# Charger_Control_Board_rev8.net
KiCad netlist of a schematic drawn in EAGLE
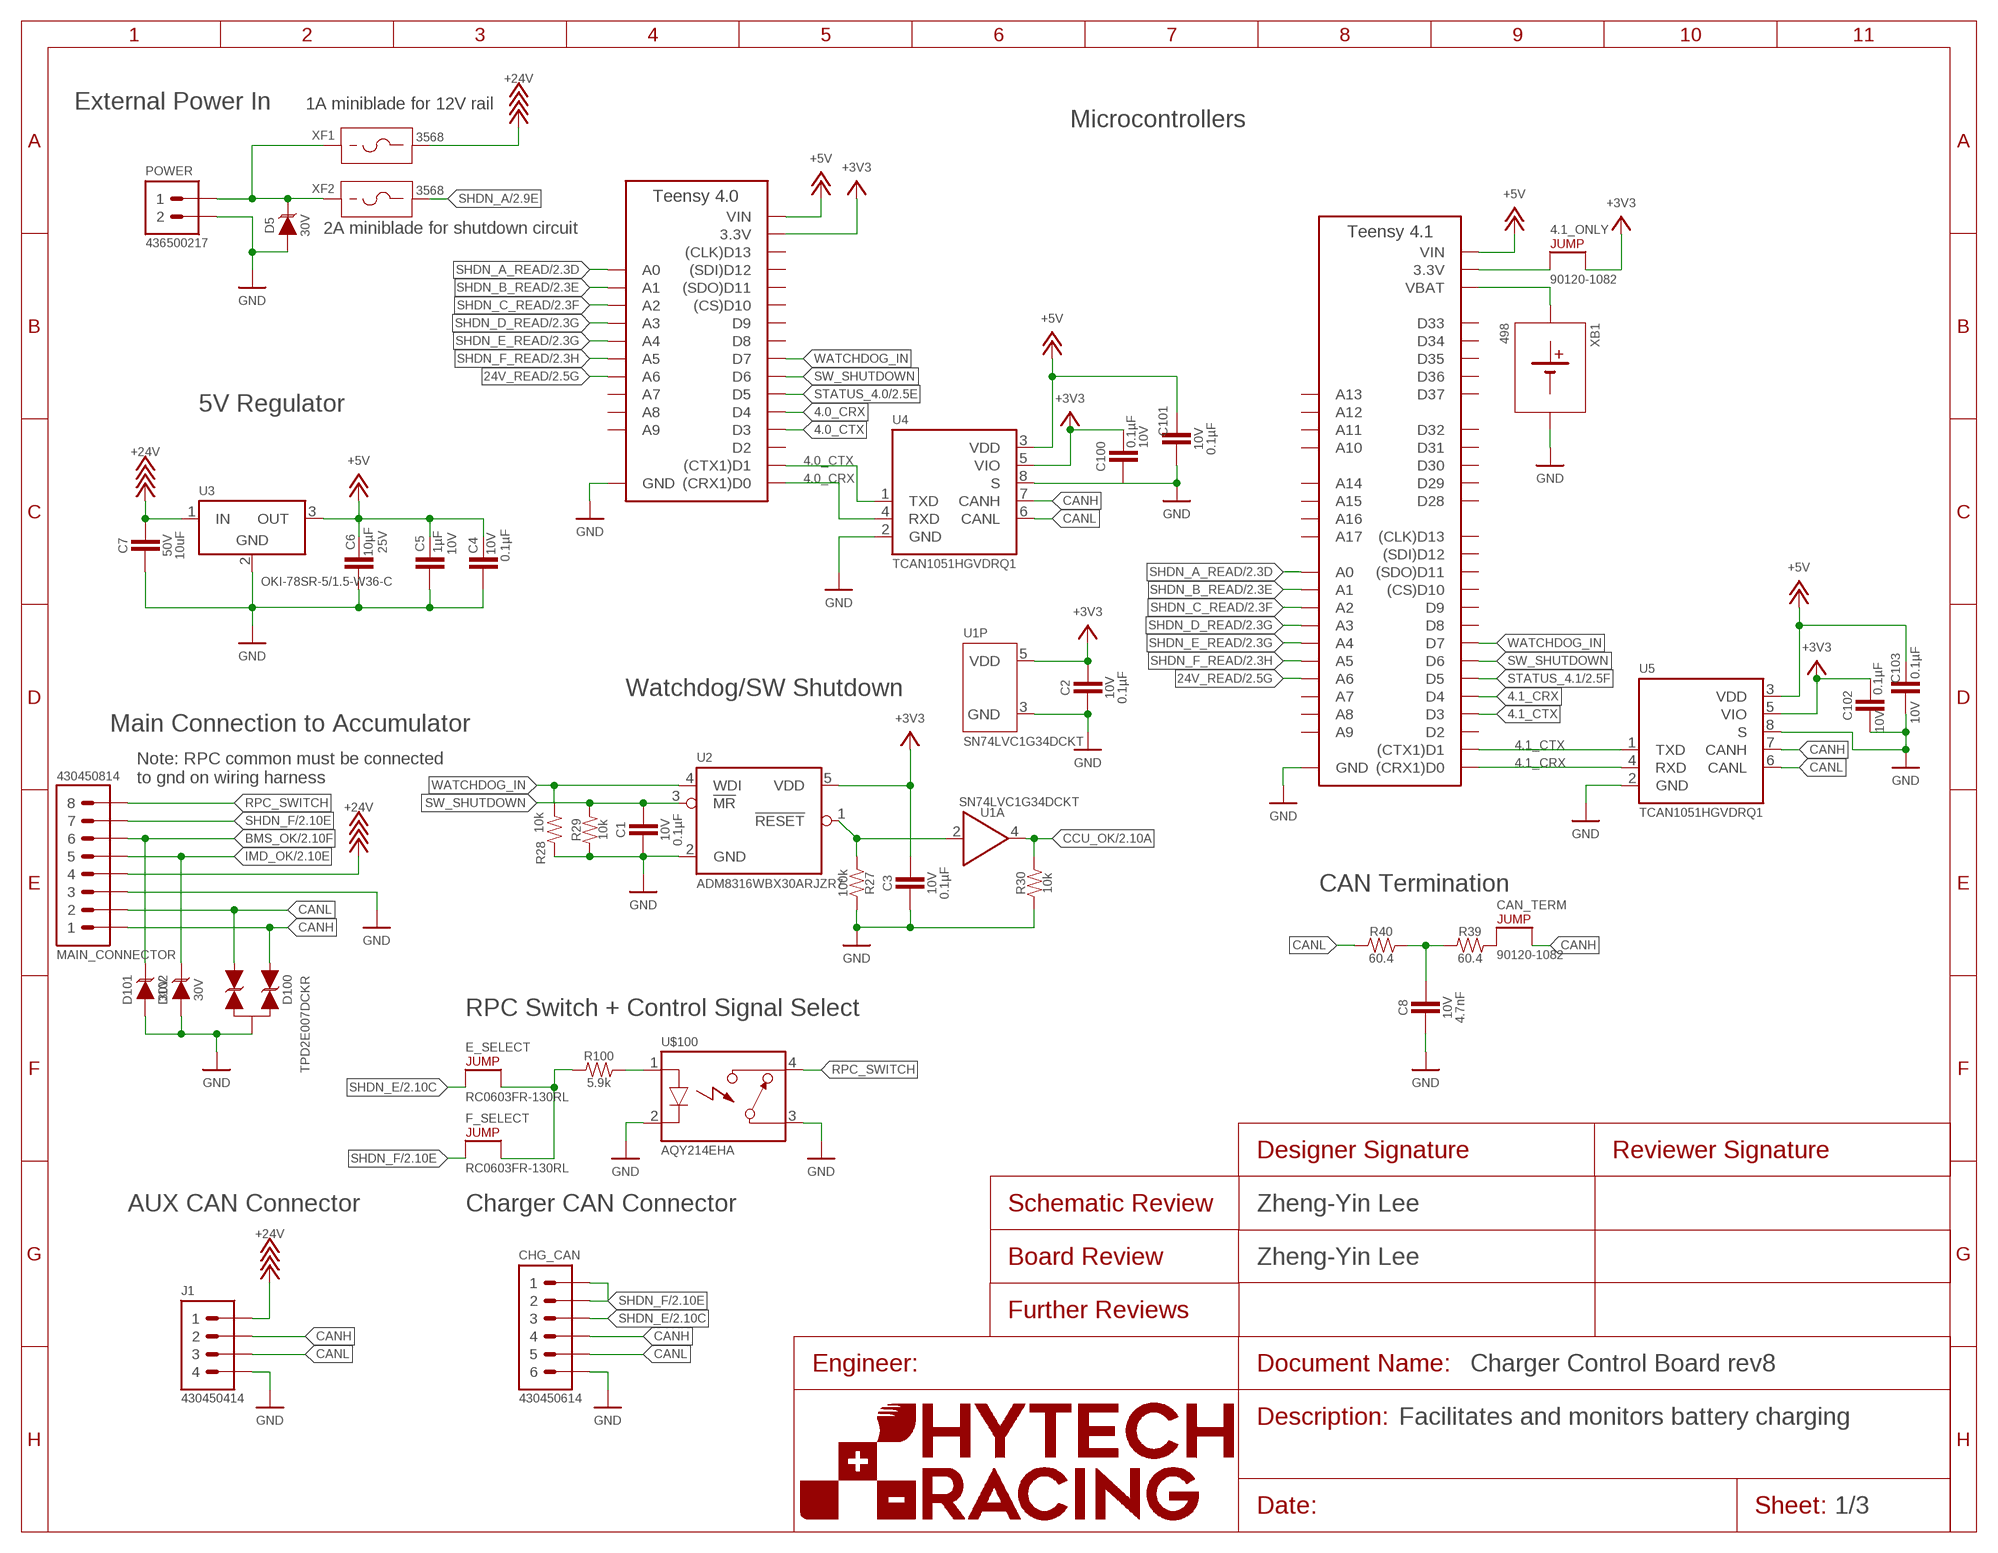
[diagram p0: schematic, sheet 1]
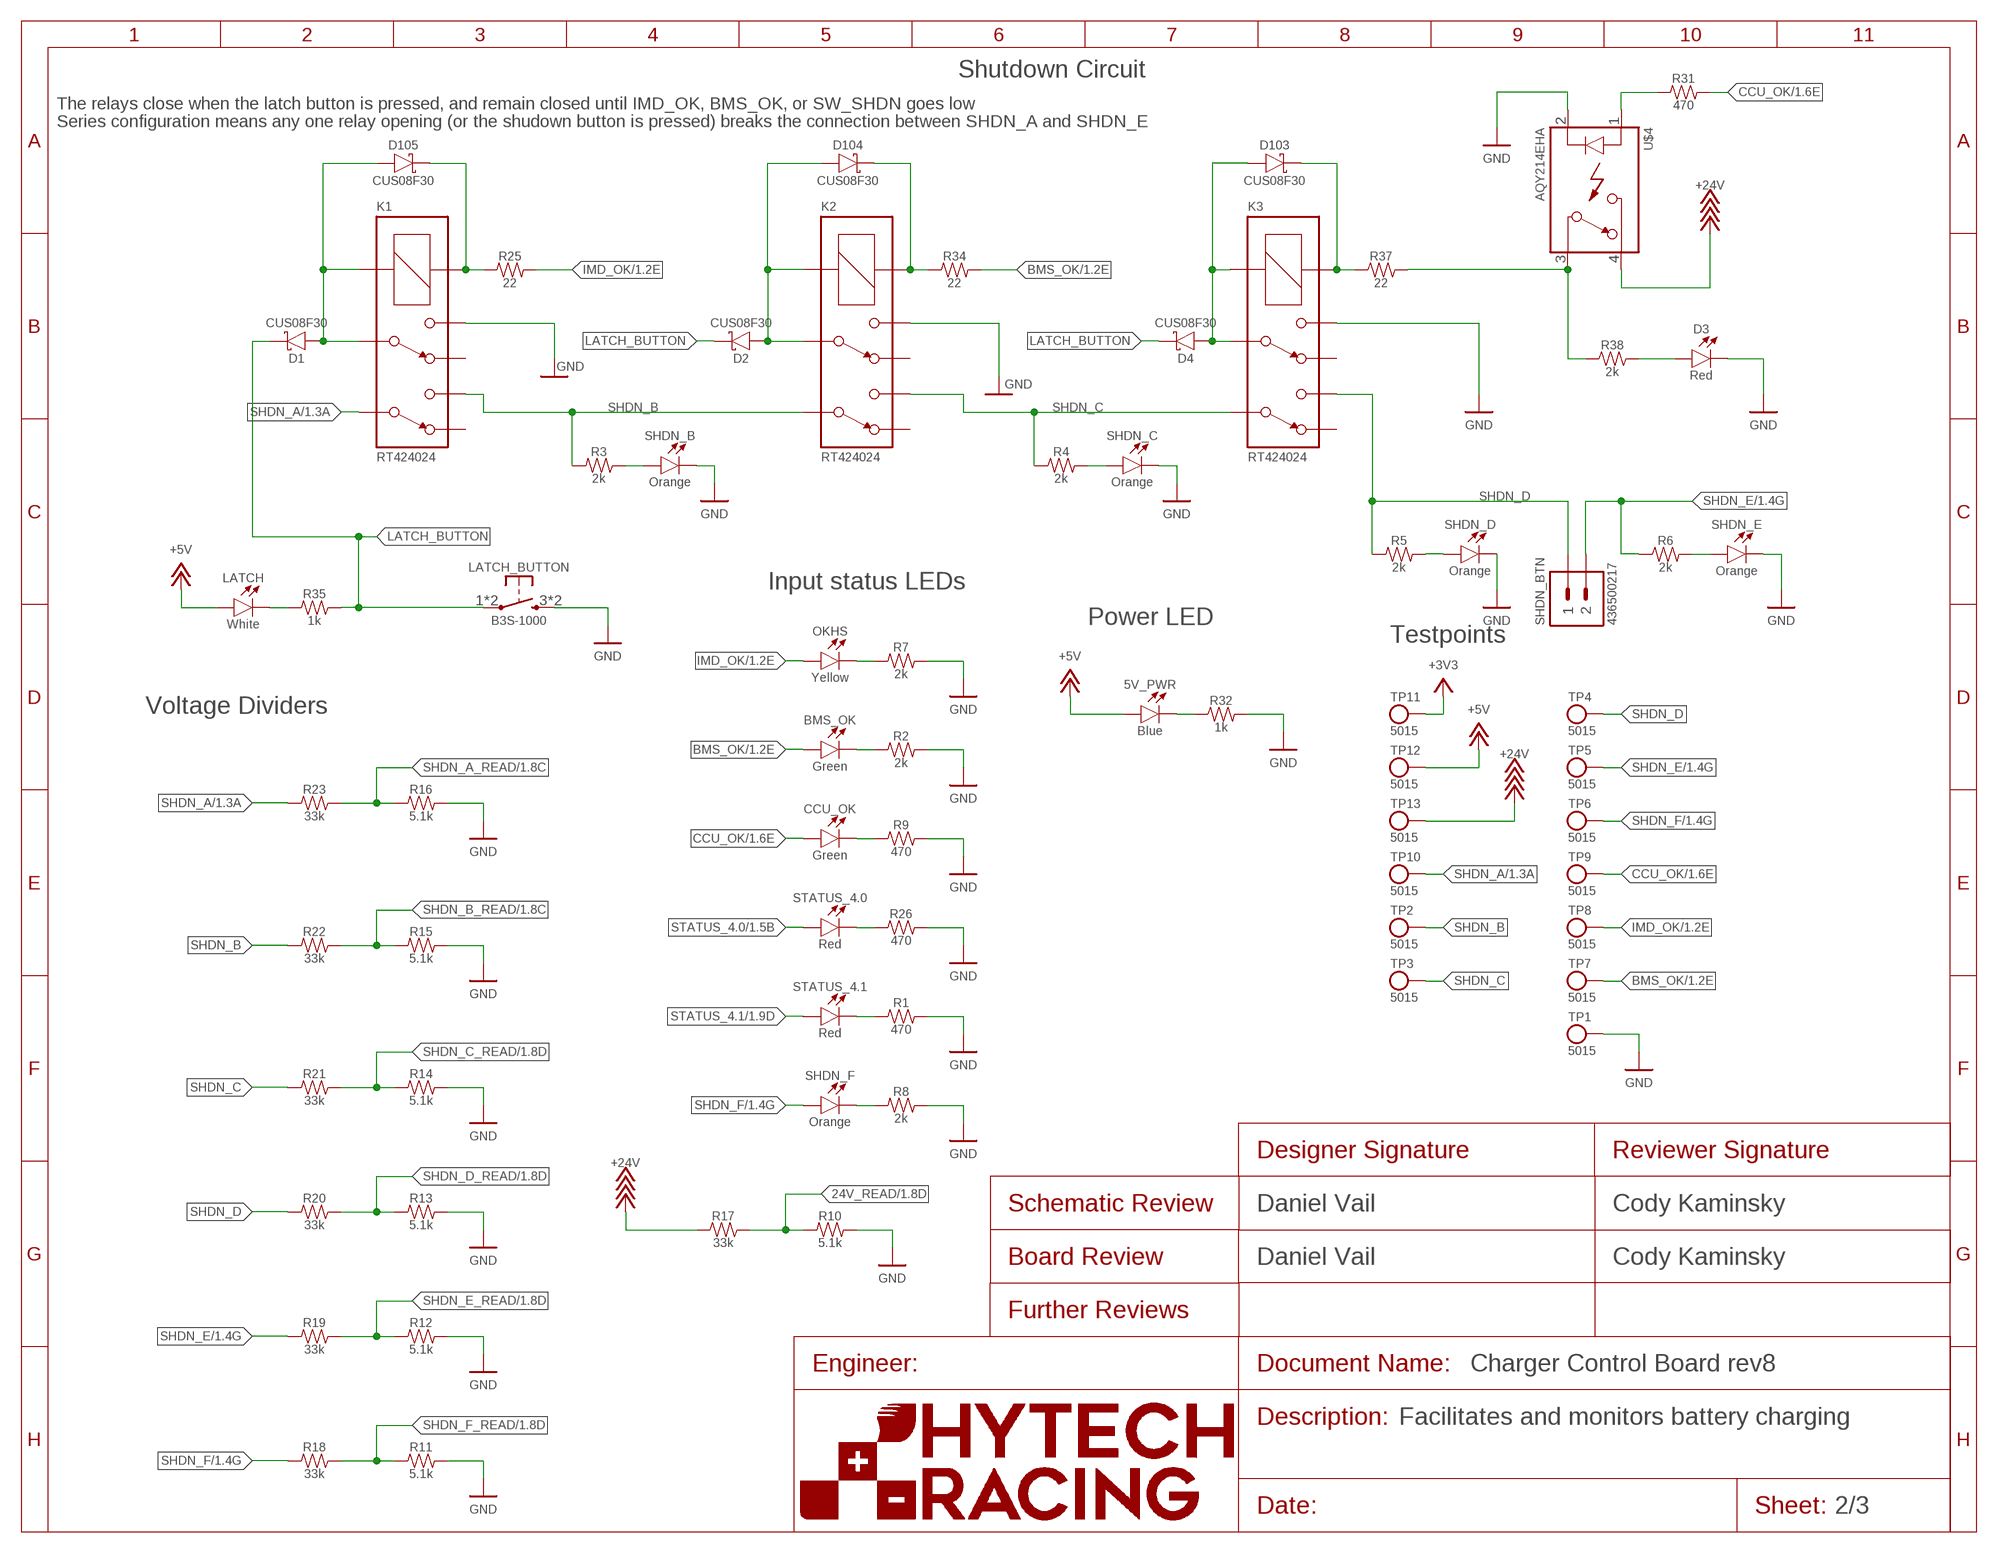
[diagram p1: schematic, sheet 2]
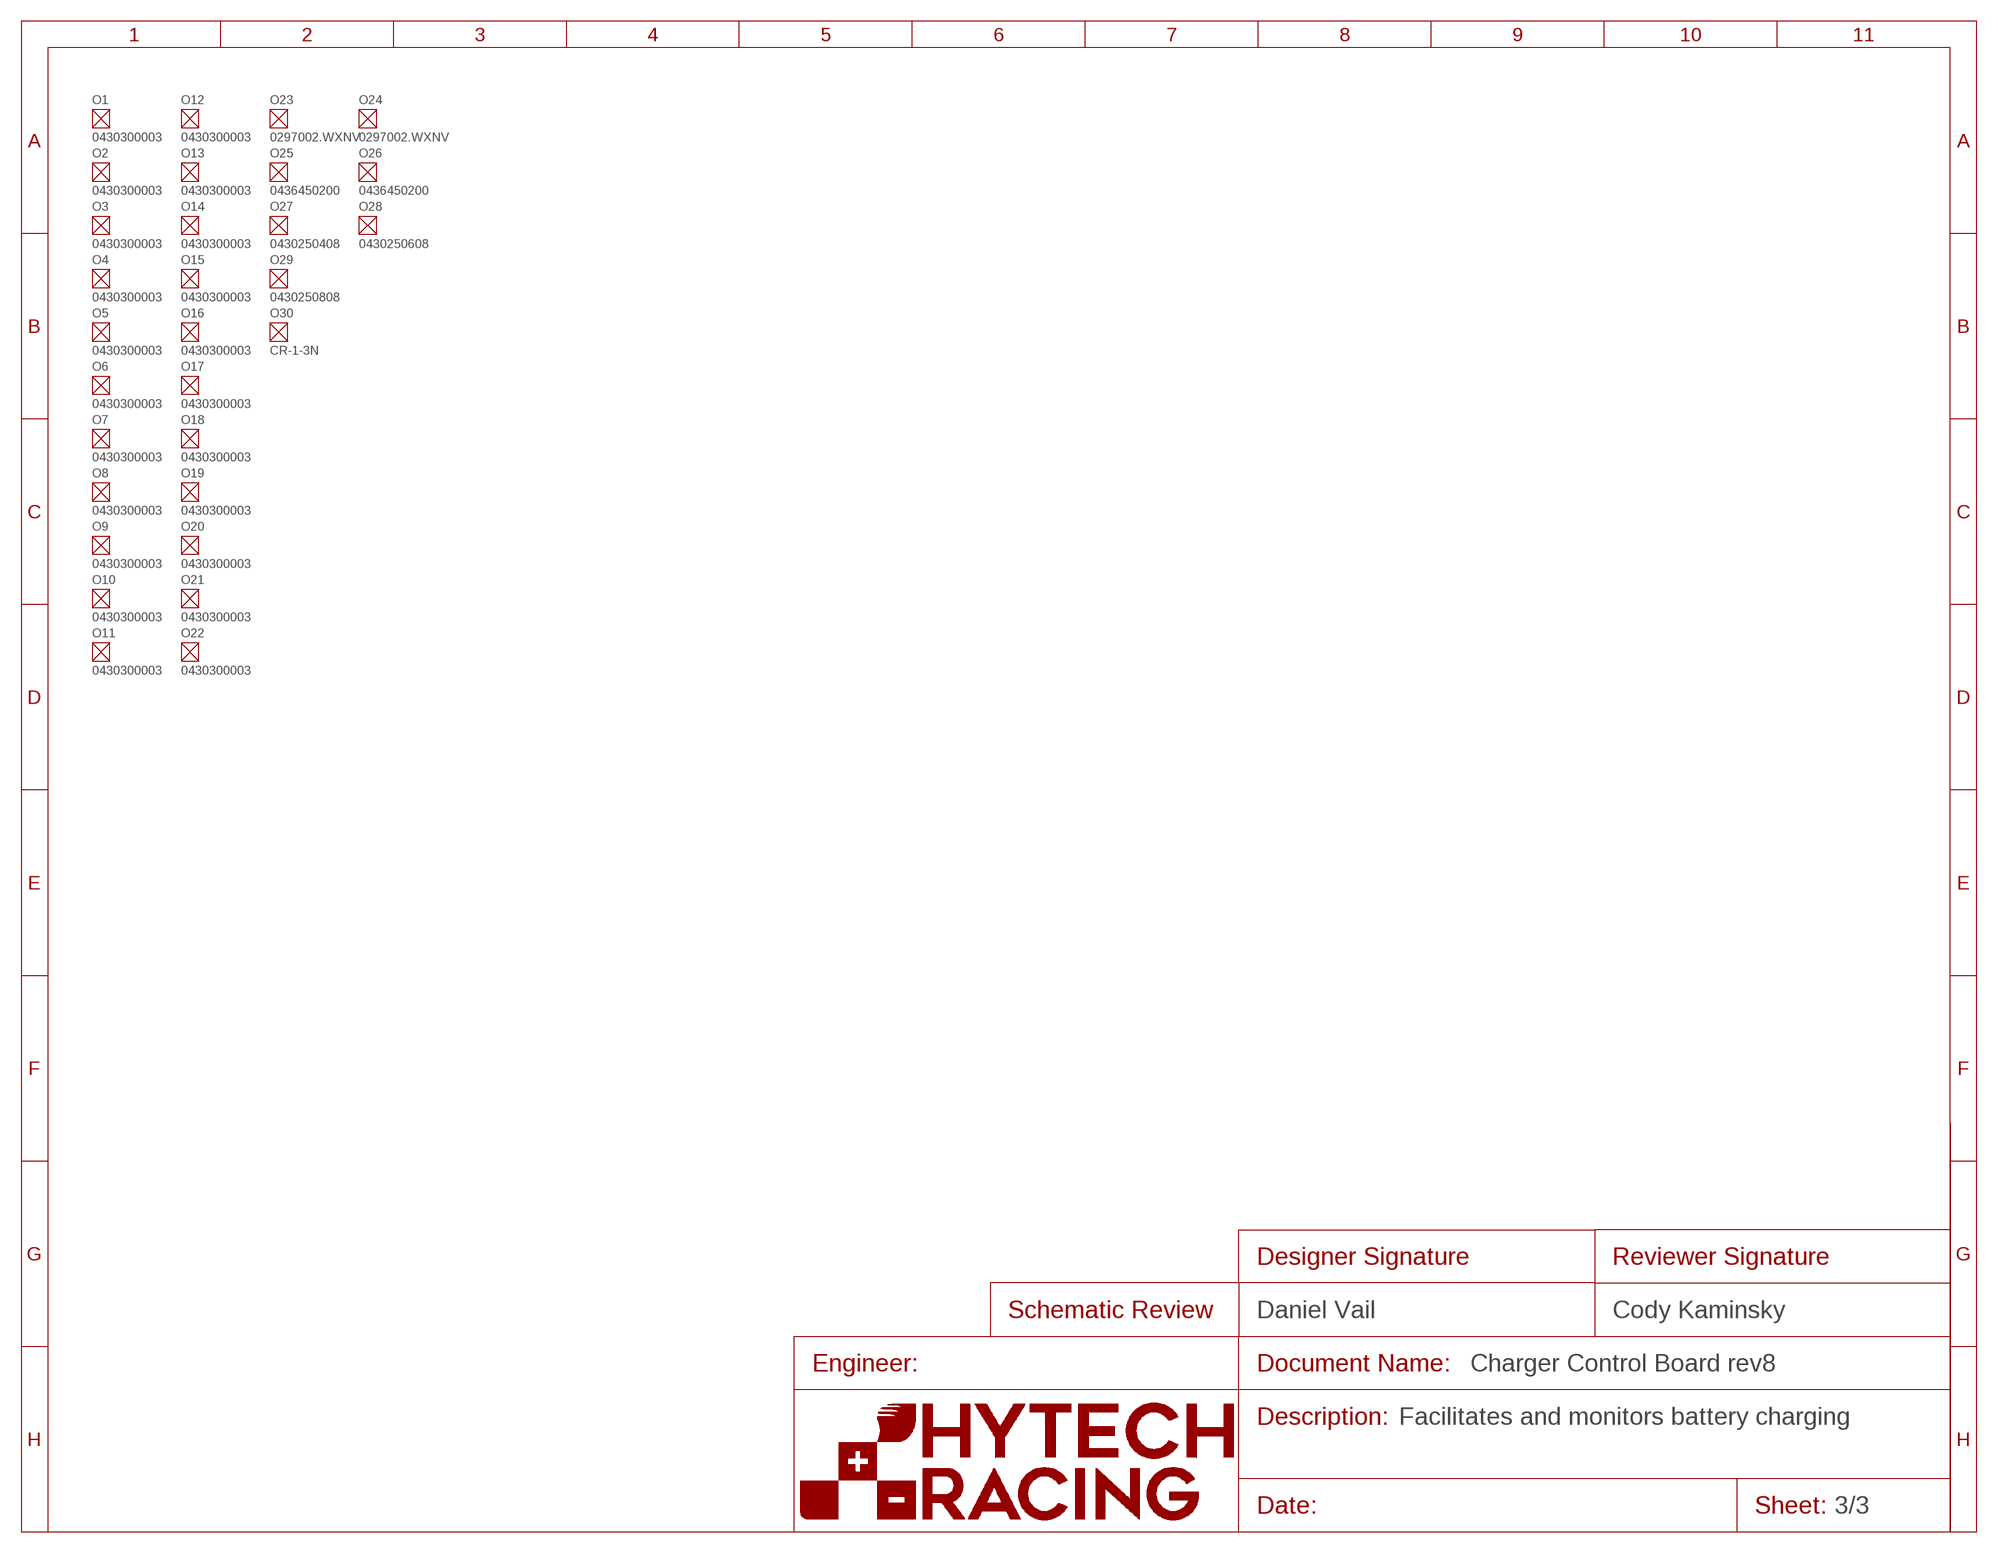
[diagram p2: schematic, sheet 3]

(export (version "E")
  (design (tool "Eeschema 10.0.6"))
  (components
    (comp (ref "4.1_ONLY")
      (value "JUMPER__1X02")
      (footprint "eagle-import:1X02")
      (fields (field (name "MANUFACTURER") "Molex") (field (name "MPN") "90120-1082 "))
      (libsource (lib "eagle-import") (part "JUMPER_?_1X02"))
    )
    (comp (ref "A1")
      (value "TEENSY_4.1")
      (footprint "eagle-import:TEENSY_LONG_EXT")
      (libsource (lib "eagle-import") (part "TEENSY_4.1"))
    )
    (comp (ref "A2")
      (value "TEENSY_4.0TH")
      (footprint "eagle-import:TEENSY_SHORT")
      (libsource (lib "eagle-import") (part "TEENSY_4.0TH"))
    )
    (comp (ref "C1")
      (value "CAPACITOR_0603_10V_0.1UF")
      (footprint "eagle-import:0603-CAP")
      (fields
        (field (name "CAPACITANCE") "0.1µF")
        (field (name "MANUFACTURER") "Vishay Vitramon")
        (field (name "MPN") "VJ0603Y104JXQPW1BC")
        (field (name "TOLERANCE") "5%")
        (field (name "VOLTAGE") "10V")
      )
      (libsource (lib "eagle-import") (part "CAPACITOR_?_060310V_0.1UF"))
    )
    (comp (ref "C2")
      (value "CAPACITOR_0603_10V_0.1UF")
      (footprint "eagle-import:0603-CAP")
      (fields
        (field (name "CAPACITANCE") "0.1µF")
        (field (name "MANUFACTURER") "Vishay Vitramon")
        (field (name "MPN") "VJ0603Y104JXQPW1BC")
        (field (name "TOLERANCE") "5%")
        (field (name "VOLTAGE") "10V")
      )
      (libsource (lib "eagle-import") (part "CAPACITOR_?_060310V_0.1UF"))
    )
    (comp (ref "C3")
      (value "CAPACITOR_0603_10V_0.1UF")
      (footprint "eagle-import:0603-CAP")
      (fields
        (field (name "CAPACITANCE") "0.1µF")
        (field (name "MANUFACTURER") "Vishay Vitramon")
        (field (name "MPN") "VJ0603Y104JXQPW1BC")
        (field (name "TOLERANCE") "5%")
        (field (name "VOLTAGE") "10V")
      )
      (libsource (lib "eagle-import") (part "CAPACITOR_?_060310V_0.1UF"))
    )
    (comp (ref "C4")
      (value "CAPACITOR_0603_10V_0.1UF")
      (footprint "eagle-import:0603-CAP")
      (fields
        (field (name "CAPACITANCE") "0.1µF")
        (field (name "MANUFACTURER") "Vishay Vitramon")
        (field (name "MPN") "VJ0603Y104JXQPW1BC")
        (field (name "TOLERANCE") "5%")
        (field (name "VOLTAGE") "10V")
      )
      (libsource (lib "eagle-import") (part "CAPACITOR_?_060310V_0.1UF"))
    )
    (comp (ref "C5")
      (value "CAPACITOR_0603_10V_1UF")
      (footprint "eagle-import:0603-CAP")
      (fields
        (field (name "CAPACITANCE") "1µF")
        (field (name "MANUFACTURER") "Yageo")
        (field (name "MPN") "CC0603KRX7R6BB105")
        (field (name "TOLERANCE") "10%")
        (field (name "VOLTAGE") "10V")
      )
      (libsource (lib "eagle-import") (part "CAPACITOR_?_060310V_1UF"))
    )
    (comp (ref "C6")
      (value "CAPACITOR_0603_25V_10UF")
      (footprint "eagle-import:0603-CAP")
      (fields
        (field (name "CAPACITANCE") "10µF")
        (field (name "MANUFACTURER") "Murata Electronics")
        (field (name "MPN") "GRM188R61E106MA73D")
        (field (name "TOLERANCE") "20%")
        (field (name "VOLTAGE") "25V")
      )
      (libsource (lib "eagle-import") (part "CAPACITOR_?_060325V_10UF"))
    )
    (comp (ref "C7")
      (value "CAPACITOR_0805_50V_10UF")
      (footprint "eagle-import:0805-CAP")
      (fields
        (field (name "CAPACITANCE") "10uF")
        (field (name "MANUFACTURER") "Murata")
        (field (name "MPN") " GRM21BR61H106KE43L")
        (field (name "TOLERANCE") "10%")
        (field (name "VOLTAGE") "50V")
      )
      (libsource (lib "eagle-import") (part "CAPACITOR_?_080550V_10UF"))
    )
    (comp (ref "C8")
      (value "CAPACITOR_0603_10V_4.7NF")
      (footprint "eagle-import:0603-CAP")
      (fields
        (field (name "CAPACITANCE") "4.7nF")
        (field (name "MANUFACTURER") "Würth Elektronik")
        (field (name "MPN") "885012206012")
        (field (name "TOLERANCE") "10%")
        (field (name "VOLTAGE") "10V")
      )
      (libsource (lib "eagle-import") (part "CAPACITOR_?_060310V_4.7NF"))
    )
    (comp (ref "C100")
      (value "CAPACITOR_0603_10V_0.1UF")
      (footprint "eagle-import:0603-CAP")
      (fields
        (field (name "CAPACITANCE") "0.1µF")
        (field (name "MANUFACTURER") "Vishay Vitramon")
        (field (name "MPN") "VJ0603Y104JXQPW1BC")
        (field (name "TOLERANCE") "5%")
        (field (name "VOLTAGE") "10V")
      )
      (libsource (lib "eagle-import") (part "CAPACITOR_?_060310V_0.1UF"))
    )
    (comp (ref "C101")
      (value "CAPACITOR_0603_10V_0.1UF")
      (footprint "eagle-import:0603-CAP")
      (fields
        (field (name "CAPACITANCE") "0.1µF")
        (field (name "MANUFACTURER") "Vishay Vitramon")
        (field (name "MPN") "VJ0603Y104JXQPW1BC")
        (field (name "TOLERANCE") "5%")
        (field (name "VOLTAGE") "10V")
      )
      (libsource (lib "eagle-import") (part "CAPACITOR_?_060310V_0.1UF"))
    )
    (comp (ref "C102")
      (value "CAPACITOR_0603_10V_0.1UF")
      (footprint "eagle-import:0603-CAP")
      (fields
        (field (name "CAPACITANCE") "0.1µF")
        (field (name "MANUFACTURER") "Vishay Vitramon")
        (field (name "MPN") "VJ0603Y104JXQPW1BC")
        (field (name "TOLERANCE") "5%")
        (field (name "VOLTAGE") "10V")
      )
      (libsource (lib "eagle-import") (part "CAPACITOR_?_060310V_0.1UF"))
    )
    (comp (ref "C103")
      (value "CAPACITOR_0603_10V_0.1UF")
      (footprint "eagle-import:0603-CAP")
      (fields
        (field (name "CAPACITANCE") "0.1µF")
        (field (name "MANUFACTURER") "Vishay Vitramon")
        (field (name "MPN") "VJ0603Y104JXQPW1BC")
        (field (name "TOLERANCE") "5%")
        (field (name "VOLTAGE") "10V")
      )
      (libsource (lib "eagle-import") (part "CAPACITOR_?_060310V_0.1UF"))
    )
    (comp (ref "CAN_TERM")
      (value "JUMPER__1X02")
      (footprint "eagle-import:1X02")
      (fields (field (name "MANUFACTURER") "Molex") (field (name "MPN") "90120-1082 "))
      (libsource (lib "eagle-import") (part "JUMPER_?_1X02"))
    )
    (comp (ref "CHG_CAN")
      (value "CONNECTOR-6_MF_T_V_")
      (footprint "eagle-import:MOLEX_MICROFIT_PTH_VERTICAL_06_DUAL")
      (fields (field (name "MPN") "430450614") (field (name "MANUFACTURER") "MOLEX"))
      (libsource (lib "eagle-import") (part "CONNECTOR-6_?_MF_T_V"))
    )
    (comp (ref "D5")
      (value "TVS_DO-214AA_30V")
      (footprint "eagle-import:DO-214AA")
      (fields
        (field (name "MANUFACTURER") "Bourns Inc.")
        (field (name "MPN") " 1.5SMBJ30A")
        (field (name "VOLTAGE") "30V")
      )
      (libsource (lib "eagle-import") (part "TVS_?_DO-214AA30V"))
    )
    (comp (ref "D100")
      (value "TVS_BIDIRECTIONAL_DUAL")
      (footprint "eagle-import:SC-70-3")
      (fields (field (name "MPN") "TPD2E007DCKR") (field (name "MANUFACTURER") "Texas Instruments"))
      (libsource (lib "eagle-import") (part "TVS_BIDIRECTIONAL_DUAL"))
    )
    (comp (ref "D101")
      (value "TVS_DO-214AA_30V")
      (footprint "eagle-import:DO-214AA")
      (fields
        (field (name "MANUFACTURER") "Bourns Inc.")
        (field (name "MPN") " 1.5SMBJ30A")
        (field (name "VOLTAGE") "30V")
      )
      (libsource (lib "eagle-import") (part "TVS_?_DO-214AA30V"))
    )
    (comp (ref "D102")
      (value "TVS_DO-214AA_30V")
      (footprint "eagle-import:DO-214AA")
      (fields
        (field (name "MANUFACTURER") "Bourns Inc.")
        (field (name "MPN") " 1.5SMBJ30A")
        (field (name "VOLTAGE") "30V")
      )
      (libsource (lib "eagle-import") (part "TVS_?_DO-214AA30V"))
    )
    (comp (ref "E_SELECT")
      (value "JUMPER_0603_")
      (footprint "eagle-import:0603-RES")
      (fields (field (name "MPN") "RC0603FR-130RL") (field (name "MANUFACTURER") "YAGEO"))
      (libsource (lib "eagle-import") (part "JUMPER_?_0603"))
    )
    (comp (ref "F_SELECT")
      (value "JUMPER_0603_")
      (footprint "eagle-import:0603-RES")
      (fields (field (name "MPN") "RC0603FR-130RL") (field (name "MANUFACTURER") "YAGEO"))
      (libsource (lib "eagle-import") (part "JUMPER_?_0603"))
    )
    (comp (ref "J1")
      (value "CONNECTOR-4_μF_T_V_BLACK")
      (footprint "eagle-import:MOLEX_MICROFIT_PTH_VERTICAL_04_DUAL")
      (fields (field (name "MANUFACTURER") "Molex") (field (name "MPN") "430450414"))
      (libsource (lib "eagle-import") (part "CONNECTOR-4_?_μF_T_VBLACK"))
    )
    (comp (ref "MAIN_CONNECTOR")
      (value "CONNECTOR-8_MF_T_V_")
      (footprint "eagle-import:MOLEX_MICROFIT_PTH_VERTICAL_08_DUAL")
      (fields (field (name "MPN") "430450814") (field (name "MANUFACTURER") "MOLEX"))
      (libsource (lib "eagle-import") (part "CONNECTOR-8_?_MF_T_V"))
    )
    (comp (ref "POWER")
      (value "CONNECTOR-2_μF_T_V_")
      (footprint "eagle-import:MOLEX_MICROFIT_PTH_VERTICAL_02_DUAL")
      (fields (field (name "MANUFACTURER") "Molex") (field (name "MPN") "436500217"))
      (libsource (lib "eagle-import") (part "CONNECTOR-2_?_μF_T_VBLACK"))
    )
    (comp (ref "R27")
      (value "RESISTOR_0603_100K")
      (footprint "eagle-import:0603-RES")
      (fields
        (field (name "MANUFACTURER") "Yageo")
        (field (name "MPN") "RC0603FR-07100KL")
        (field (name "POWER") "0.1W")
        (field (name "RESISTANCE") "100k")
      )
      (libsource (lib "eagle-import") (part "RESISTOR_?_0603100K"))
    )
    (comp (ref "R28")
      (value "RESISTOR_0603_10K")
      (footprint "eagle-import:0603-RES")
      (fields
        (field (name "MANUFACTURER") "Panasonic Electronic Components")
        (field (name "MPN") "ERA-3ARB103V")
        (field (name "POWER") "0.1W")
        (field (name "RESISTANCE") "10k")
      )
      (libsource (lib "eagle-import") (part "RESISTOR_?_060310K"))
    )
    (comp (ref "R29")
      (value "RESISTOR_0603_10K")
      (footprint "eagle-import:0603-RES")
      (fields
        (field (name "MANUFACTURER") "Panasonic Electronic Components")
        (field (name "MPN") "ERA-3ARB103V")
        (field (name "POWER") "0.1W")
        (field (name "RESISTANCE") "10k")
      )
      (libsource (lib "eagle-import") (part "RESISTOR_?_060310K"))
    )
    (comp (ref "R30")
      (value "RESISTOR_0603_10K")
      (footprint "eagle-import:0603-RES")
      (fields
        (field (name "MANUFACTURER") "Panasonic Electronic Components")
        (field (name "MPN") "ERA-3ARB103V")
        (field (name "POWER") "0.1W")
        (field (name "RESISTANCE") "10k")
      )
      (libsource (lib "eagle-import") (part "RESISTOR_?_060310K"))
    )
    (comp (ref "R39")
      (value "RESISTOR_0603_60.4")
      (footprint "eagle-import:0603-RES")
      (fields
        (field (name "MANUFACTURER") "Yageo")
        (field (name "MPN") "RC0603FR-0760R4L")
        (field (name "POWER") "0.1W")
        (field (name "RESISTANCE") "60.4")
      )
      (libsource (lib "eagle-import") (part "RESISTOR_?_060360.4"))
    )
    (comp (ref "R40")
      (value "RESISTOR_0603_60.4")
      (footprint "eagle-import:0603-RES")
      (fields
        (field (name "MANUFACTURER") "Yageo")
        (field (name "MPN") "RC0603FR-0760R4L")
        (field (name "POWER") "0.1W")
        (field (name "RESISTANCE") "60.4")
      )
      (libsource (lib "eagle-import") (part "RESISTOR_?_060360.4"))
    )
    (comp (ref "R100")
      (value "RESISTOR_0603_5.9K")
      (footprint "eagle-import:0603-RES")
      (fields
        (field (name "MANUFACTURER") "Panasonic Electronic Components")
        (field (name "MPN") "ERA-3AEB5901V")
        (field (name "POWER") "0.1W")
        (field (name "RESISTANCE") "5.9k")
      )
      (libsource (lib "eagle-import") (part "RESISTOR_?_06035.9K"))
    )
    (comp (ref "U$100")
      (value "RELAY_SOLIDSTATE_NO_DIP-4")
      (footprint "eagle-import:DIP-4")
      (fields (field (name "MPN") "AQY214EHA") (field (name "MANUFACTURER") "Panasonic"))
      (libsource (lib "eagle-import") (part "RELAY_SOLIDSTATE_NO_DIP-4"))
    )
    (comp (ref "U1")
      (value "LOGICGATE_BUFFER")
      (footprint "eagle-import:SC-70-5")
      (fields (field (name "MANUFACTURER") "Texas Instruments"))
      (libsource (lib "eagle-import") (part "LOGICGATE_BUFFER"))
    )
    (comp (ref "U2")
      (value "ADM8316WBX30")
      (footprint "eagle-import:SOT-23-5")
      (fields (field (name "MANUFACTURER") "Analog Devices Inc.") (field (name "MPN") "ADM8316WBX30ARJZR7"))
      (libsource (lib "eagle-import") (part "ADM8316WBX30"))
    )
    (comp (ref "U3")
      (value "VOLTAGE_REGULATOR_MODULE_OKI-78SR_5V")
      (footprint "eagle-import:OKI-78SR")
      (fields
        (field (name "MANUFACTURER") "Murata Power Solutions Inc.")
        (field (name "MPN") "OKI-78SR-5/1.5-W36-C")
      )
      (libsource (lib "eagle-import") (part "VOLTAGE_REGULATOR_MODULE_?_OKI-78SR5V"))
    )
    (comp (ref "U4")
      (value "TCAN1051HQV-Q1")
      (footprint "eagle-import:SOIC-08(NARROW,0.15_)")
      (fields (field (name "MANUFACTURER") "Texas Instruments") (field (name "MPN") "TCAN1051HGVDRQ1"))
      (libsource (lib "eagle-import") (part "TCAN1051V-Q1HQ"))
    )
    (comp (ref "U5")
      (value "TCAN1051HQV-Q1")
      (footprint "eagle-import:SOIC-08(NARROW,0.15_)")
      (fields (field (name "MANUFACTURER") "Texas Instruments") (field (name "MPN") "TCAN1051HGVDRQ1"))
      (libsource (lib "eagle-import") (part "TCAN1051V-Q1HQ"))
    )
    (comp (ref "XB1")
      (value "BATTERY_HOLDER_KEYSTONE_498")
      (footprint "eagle-import:498")
      (fields (field (name "MPN") "498") (field (name "MANUFACTURER") "Keystone Electronics"))
      (libsource (lib "eagle-import") (part "BATTERY_HOLDER_KEYSTONE_498"))
    )
    (comp (ref "XF1")
      (value "FUSE_HOLDER_MINIBLADEPTH")
      (footprint "eagle-import:3568")
      (fields (field (name "MANUFACTURER") "Keystone") (field (name "MPN") "3568"))
      (libsource (lib "eagle-import") (part "FUSE_HOLDER_PTHMINIBLADE"))
    )
    (comp (ref "XF2")
      (value "FUSE_HOLDER_MINIBLADEPTH")
      (footprint "eagle-import:3568")
      (fields (field (name "MANUFACTURER") "Keystone") (field (name "MPN") "3568"))
      (libsource (lib "eagle-import") (part "FUSE_HOLDER_PTHMINIBLADE"))
    )
    (comp (ref "5V_PWR")
      (value "LED_0603_BLUE")
      (footprint "eagle-import:0603-LED")
      (fields
        (field (name "COLOR") "Blue")
        (field (name "MANUFACTURER") "Kingbright")
        (field (name "MPN") "APT1608VBC/D")
      )
      (libsource (lib "eagle-import") (part "LED_?_0603BLUE"))
    )
    (comp (ref "BMS_OK")
      (value "LED_0603_GREEN")
      (footprint "eagle-import:0603-LED")
      (fields
        (field (name "COLOR") "Green")
        (field (name "MANUFACTURER") "Kingbright")
        (field (name "MPN") "APT1608ZGCK")
      )
      (libsource (lib "eagle-import") (part "LED_?_0603GREEN"))
    )
    (comp (ref "CCU_OK")
      (value "LED_0603_GREEN")
      (footprint "eagle-import:0603-LED")
      (fields
        (field (name "COLOR") "Green")
        (field (name "MANUFACTURER") "Kingbright")
        (field (name "MPN") "APT1608ZGCK")
      )
      (libsource (lib "eagle-import") (part "LED_?_0603GREEN"))
    )
    (comp (ref "D1")
      (value "SCHOTTKY_SOD323_30V")
      (footprint "eagle-import:SOD-323")
      (fields
        (field (name "MANUFACTURER") "Toshiba Semiconductor and Storage")
        (field (name "MPN") "CUS08F30")
        (field (name "VOLTAGE") "30V")
      )
      (libsource (lib "eagle-import") (part "SCHOTTKY_?_SOD32330V"))
    )
    (comp (ref "D2")
      (value "SCHOTTKY_SOD323_30V")
      (footprint "eagle-import:SOD-323")
      (fields
        (field (name "MANUFACTURER") "Toshiba Semiconductor and Storage")
        (field (name "MPN") "CUS08F30")
        (field (name "VOLTAGE") "30V")
      )
      (libsource (lib "eagle-import") (part "SCHOTTKY_?_SOD32330V"))
    )
    (comp (ref "D3")
      (value "LED_0603_RED")
      (footprint "eagle-import:0603-LED")
      (fields
        (field (name "COLOR") "Red")
        (field (name "MANUFACTURER") "Kingbright")
        (field (name "MPN") "APT1608SECK/J3-PRV")
      )
      (libsource (lib "eagle-import") (part "LED_?_0603RED"))
    )
    (comp (ref "D4")
      (value "SCHOTTKY_SOD323_30V")
      (footprint "eagle-import:SOD-323")
      (fields
        (field (name "MANUFACTURER") "Toshiba Semiconductor and Storage")
        (field (name "MPN") "CUS08F30")
        (field (name "VOLTAGE") "30V")
      )
      (libsource (lib "eagle-import") (part "SCHOTTKY_?_SOD32330V"))
    )
    (comp (ref "D103")
      (value "SCHOTTKY_SOD323_30V")
      (footprint "eagle-import:SOD-323")
      (fields
        (field (name "MANUFACTURER") "Toshiba Semiconductor and Storage")
        (field (name "MPN") "CUS08F30")
        (field (name "VOLTAGE") "30V")
      )
      (libsource (lib "eagle-import") (part "SCHOTTKY_?_SOD32330V"))
    )
    (comp (ref "D104")
      (value "SCHOTTKY_SOD323_30V")
      (footprint "eagle-import:SOD-323")
      (fields
        (field (name "MANUFACTURER") "Toshiba Semiconductor and Storage")
        (field (name "MPN") "CUS08F30")
        (field (name "VOLTAGE") "30V")
      )
      (libsource (lib "eagle-import") (part "SCHOTTKY_?_SOD32330V"))
    )
    (comp (ref "D105")
      (value "SCHOTTKY_SOD323_30V")
      (footprint "eagle-import:SOD-323")
      (fields
        (field (name "MANUFACTURER") "Toshiba Semiconductor and Storage")
        (field (name "MPN") "CUS08F30")
        (field (name "VOLTAGE") "30V")
      )
      (libsource (lib "eagle-import") (part "SCHOTTKY_?_SOD32330V"))
    )
    (comp (ref "K1")
      (value "RELAY_DPDT_RT424024TH")
      (footprint "eagle-import:RT_2_")
      (fields (field (name "MANUFACTURER") "TE Connectivity") (field (name "MPN") "RT424024"))
      (libsource (lib "eagle-import") (part "RELAY_DPDT_THRT424024"))
    )
    (comp (ref "K2")
      (value "RELAY_DPDT_RT424024TH")
      (footprint "eagle-import:RT_2_")
      (fields (field (name "MANUFACTURER") "TE Connectivity") (field (name "MPN") "RT424024"))
      (libsource (lib "eagle-import") (part "RELAY_DPDT_THRT424024"))
    )
    (comp (ref "K3")
      (value "RELAY_DPDT_RT424024TH")
      (footprint "eagle-import:RT_2_")
      (fields (field (name "MANUFACTURER") "TE Connectivity") (field (name "MPN") "RT424024"))
      (libsource (lib "eagle-import") (part "RELAY_DPDT_THRT424024"))
    )
    (comp (ref "LATCH")
      (value "LED_0603_WHITE")
      (footprint "eagle-import:0603-LED")
      (fields
        (field (name "COLOR") "White")
        (field (name "MANUFACTURER") "Bivar Inc.")
        (field (name "MPN") "SM0603UWC")
      )
      (libsource (lib "eagle-import") (part "LED_?_0603WHITE"))
    )
    (comp (ref "LATCH_BUTTON")
      (value "BUTTON")
      (footprint "eagle-import:B3S-100X")
      (fields (field (name "MPN") "B3S-1000") (field (name "MANUFACTURER") "Omron"))
      (libsource (lib "eagle-import") (part "BUTTON"))
    )
    (comp (ref "OKHS")
      (value "LED_0603_YELLOW")
      (footprint "eagle-import:0603-LED")
      (fields
        (field (name "COLOR") "Yellow")
        (field (name "MANUFACTURER") "Kingbright")
        (field (name "MPN") "APT1608SYCK/J3-PRV")
      )
      (libsource (lib "eagle-import") (part "LED_?_0603YELLOW"))
    )
    (comp (ref "R1")
      (value "RESISTOR_0603_470")
      (footprint "eagle-import:0603-RES")
      (fields
        (field (name "MANUFACTURER") "Panasonic Electronic Components")
        (field (name "MPN") "ERJ-PA3F4700V")
        (field (name "POWER") "0.25W")
        (field (name "RESISTANCE") "470")
      )
      (libsource (lib "eagle-import") (part "RESISTOR_?_0603470"))
    )
    (comp (ref "R2")
      (value "RESISTOR_0603_2K")
      (footprint "eagle-import:0603-RES")
      (fields
        (field (name "MANUFACTURER") "Panasonic Electronic Components")
        (field (name "MPN") "ERJ-UP3F2001V")
        (field (name "POWER") "0.25W")
        (field (name "RESISTANCE") "2k")
      )
      (libsource (lib "eagle-import") (part "RESISTOR_?_06032K"))
    )
    (comp (ref "R3")
      (value "RESISTOR_0603_2K")
      (footprint "eagle-import:0603-RES")
      (fields
        (field (name "MANUFACTURER") "Panasonic Electronic Components")
        (field (name "MPN") "ERJ-UP3F2001V")
        (field (name "POWER") "0.25W")
        (field (name "RESISTANCE") "2k")
      )
      (libsource (lib "eagle-import") (part "RESISTOR_?_06032K"))
    )
    (comp (ref "R4")
      (value "RESISTOR_0603_2K")
      (footprint "eagle-import:0603-RES")
      (fields
        (field (name "MANUFACTURER") "Panasonic Electronic Components")
        (field (name "MPN") "ERJ-UP3F2001V")
        (field (name "POWER") "0.25W")
        (field (name "RESISTANCE") "2k")
      )
      (libsource (lib "eagle-import") (part "RESISTOR_?_06032K"))
    )
    (comp (ref "R5")
      (value "RESISTOR_0603_2K")
      (footprint "eagle-import:0603-RES")
      (fields
        (field (name "MANUFACTURER") "Panasonic Electronic Components")
        (field (name "MPN") "ERJ-UP3F2001V")
        (field (name "POWER") "0.25W")
        (field (name "RESISTANCE") "2k")
      )
      (libsource (lib "eagle-import") (part "RESISTOR_?_06032K"))
    )
    (comp (ref "R6")
      (value "RESISTOR_0603_2K")
      (footprint "eagle-import:0603-RES")
      (fields
        (field (name "MANUFACTURER") "Panasonic Electronic Components")
        (field (name "MPN") "ERJ-UP3F2001V")
        (field (name "POWER") "0.25W")
        (field (name "RESISTANCE") "2k")
      )
      (libsource (lib "eagle-import") (part "RESISTOR_?_06032K"))
    )
    (comp (ref "R7")
      (value "RESISTOR_0603_2K")
      (footprint "eagle-import:0603-RES")
      (fields
        (field (name "MANUFACTURER") "Panasonic Electronic Components")
        (field (name "MPN") "ERJ-UP3F2001V")
        (field (name "POWER") "0.25W")
        (field (name "RESISTANCE") "2k")
      )
      (libsource (lib "eagle-import") (part "RESISTOR_?_06032K"))
    )
    (comp (ref "R8")
      (value "RESISTOR_0603_2K")
      (footprint "eagle-import:0603-RES")
      (fields
        (field (name "MANUFACTURER") "Panasonic Electronic Components")
        (field (name "MPN") "ERJ-UP3F2001V")
        (field (name "POWER") "0.25W")
        (field (name "RESISTANCE") "2k")
      )
      (libsource (lib "eagle-import") (part "RESISTOR_?_06032K"))
    )
    (comp (ref "R9")
      (value "RESISTOR_0603_470")
      (footprint "eagle-import:0603-RES")
      (fields
        (field (name "MANUFACTURER") "Panasonic Electronic Components")
        (field (name "MPN") "ERJ-PA3F4700V")
        (field (name "POWER") "0.25W")
        (field (name "RESISTANCE") "470")
      )
      (libsource (lib "eagle-import") (part "RESISTOR_?_0603470"))
    )
    (comp (ref "R10")
      (value "RESISTOR_0603_5.1K")
      (footprint "eagle-import:0603-RES")
      (fields
        (field (name "MANUFACTURER") "Yageo")
        (field (name "MPN") "RC0603FR-075K1L")
        (field (name "POWER") "0.1W")
        (field (name "RESISTANCE") "5.1k")
      )
      (libsource (lib "eagle-import") (part "RESISTOR_?_06035.1K"))
    )
    (comp (ref "R11")
      (value "RESISTOR_0603_5.1K")
      (footprint "eagle-import:0603-RES")
      (fields
        (field (name "MANUFACTURER") "Yageo")
        (field (name "MPN") "RC0603FR-075K1L")
        (field (name "POWER") "0.1W")
        (field (name "RESISTANCE") "5.1k")
      )
      (libsource (lib "eagle-import") (part "RESISTOR_?_06035.1K"))
    )
    (comp (ref "R12")
      (value "RESISTOR_0603_5.1K")
      (footprint "eagle-import:0603-RES")
      (fields
        (field (name "MANUFACTURER") "Yageo")
        (field (name "MPN") "RC0603FR-075K1L")
        (field (name "POWER") "0.1W")
        (field (name "RESISTANCE") "5.1k")
      )
      (libsource (lib "eagle-import") (part "RESISTOR_?_06035.1K"))
    )
    (comp (ref "R13")
      (value "RESISTOR_0603_5.1K")
      (footprint "eagle-import:0603-RES")
      (fields
        (field (name "MANUFACTURER") "Yageo")
        (field (name "MPN") "RC0603FR-075K1L")
        (field (name "POWER") "0.1W")
        (field (name "RESISTANCE") "5.1k")
      )
      (libsource (lib "eagle-import") (part "RESISTOR_?_06035.1K"))
    )
    (comp (ref "R14")
      (value "RESISTOR_0603_5.1K")
      (footprint "eagle-import:0603-RES")
      (fields
        (field (name "MANUFACTURER") "Yageo")
        (field (name "MPN") "RC0603FR-075K1L")
        (field (name "POWER") "0.1W")
        (field (name "RESISTANCE") "5.1k")
      )
      (libsource (lib "eagle-import") (part "RESISTOR_?_06035.1K"))
    )
    (comp (ref "R15")
      (value "RESISTOR_0603_5.1K")
      (footprint "eagle-import:0603-RES")
      (fields
        (field (name "MANUFACTURER") "Yageo")
        (field (name "MPN") "RC0603FR-075K1L")
        (field (name "POWER") "0.1W")
        (field (name "RESISTANCE") "5.1k")
      )
      (libsource (lib "eagle-import") (part "RESISTOR_?_06035.1K"))
    )
    (comp (ref "R16")
      (value "RESISTOR_0603_5.1K")
      (footprint "eagle-import:0603-RES")
      (fields
        (field (name "MANUFACTURER") "Yageo")
        (field (name "MPN") "RC0603FR-075K1L")
        (field (name "POWER") "0.1W")
        (field (name "RESISTANCE") "5.1k")
      )
      (libsource (lib "eagle-import") (part "RESISTOR_?_06035.1K"))
    )
    (comp (ref "R17")
      (value "RESISTOR_0603_33K")
      (footprint "eagle-import:0603-RES")
      (fields
        (field (name "MANUFACTURER") "Rohm Semiconductor")
        (field (name "MPN") "KTR03EZPF3302")
        (field (name "POWER") "0.1W")
        (field (name "RESISTANCE") "33k")
      )
      (libsource (lib "eagle-import") (part "RESISTOR_?_060333K"))
    )
    (comp (ref "R18")
      (value "RESISTOR_0603_33K")
      (footprint "eagle-import:0603-RES")
      (fields
        (field (name "MANUFACTURER") "Rohm Semiconductor")
        (field (name "MPN") "KTR03EZPF3302")
        (field (name "POWER") "0.1W")
        (field (name "RESISTANCE") "33k")
      )
      (libsource (lib "eagle-import") (part "RESISTOR_?_060333K"))
    )
    (comp (ref "R19")
      (value "RESISTOR_0603_33K")
      (footprint "eagle-import:0603-RES")
      (fields
        (field (name "MANUFACTURER") "Rohm Semiconductor")
        (field (name "MPN") "KTR03EZPF3302")
        (field (name "POWER") "0.1W")
        (field (name "RESISTANCE") "33k")
      )
      (libsource (lib "eagle-import") (part "RESISTOR_?_060333K"))
    )
    (comp (ref "R20")
      (value "RESISTOR_0603_33K")
      (footprint "eagle-import:0603-RES")
      (fields
        (field (name "MANUFACTURER") "Rohm Semiconductor")
        (field (name "MPN") "KTR03EZPF3302")
        (field (name "POWER") "0.1W")
        (field (name "RESISTANCE") "33k")
      )
      (libsource (lib "eagle-import") (part "RESISTOR_?_060333K"))
    )
    (comp (ref "R21")
      (value "RESISTOR_0603_33K")
      (footprint "eagle-import:0603-RES")
      (fields
        (field (name "MANUFACTURER") "Rohm Semiconductor")
        (field (name "MPN") "KTR03EZPF3302")
        (field (name "POWER") "0.1W")
        (field (name "RESISTANCE") "33k")
      )
      (libsource (lib "eagle-import") (part "RESISTOR_?_060333K"))
    )
    (comp (ref "R22")
      (value "RESISTOR_0603_33K")
      (footprint "eagle-import:0603-RES")
      (fields
        (field (name "MANUFACTURER") "Rohm Semiconductor")
        (field (name "MPN") "KTR03EZPF3302")
        (field (name "POWER") "0.1W")
        (field (name "RESISTANCE") "33k")
      )
      (libsource (lib "eagle-import") (part "RESISTOR_?_060333K"))
    )
    (comp (ref "R23")
      (value "RESISTOR_0603_33K")
      (footprint "eagle-import:0603-RES")
      (fields
        (field (name "MANUFACTURER") "Rohm Semiconductor")
        (field (name "MPN") "KTR03EZPF3302")
        (field (name "POWER") "0.1W")
        (field (name "RESISTANCE") "33k")
      )
      (libsource (lib "eagle-import") (part "RESISTOR_?_060333K"))
    )
    (comp (ref "R25")
      (value "RESISTOR_0603_22")
      (footprint "eagle-import:0603-RES")
      (fields
        (field (name "MANUFACTURER") "Yageo")
        (field (name "MPN") "RC0603FR-0722RL")
        (field (name "POWER") "0.1W")
        (field (name "RESISTANCE") "22")
      )
      (libsource (lib "eagle-import") (part "RESISTOR_?_060322"))
    )
    (comp (ref "R26")
      (value "RESISTOR_0603_470")
      (footprint "eagle-import:0603-RES")
      (fields
        (field (name "MANUFACTURER") "Panasonic Electronic Components")
        (field (name "MPN") "ERJ-PA3F4700V")
        (field (name "POWER") "0.25W")
        (field (name "RESISTANCE") "470")
      )
      (libsource (lib "eagle-import") (part "RESISTOR_?_0603470"))
    )
    (comp (ref "R31")
      (value "RESISTOR_0603_470")
      (footprint "eagle-import:0603-RES")
      (fields
        (field (name "MANUFACTURER") "Panasonic Electronic Components")
        (field (name "MPN") "ERJ-PA3F4700V")
        (field (name "POWER") "0.25W")
        (field (name "RESISTANCE") "470")
      )
      (libsource (lib "eagle-import") (part "RESISTOR_?_0603470"))
    )
    (comp (ref "R32")
      (value "RESISTOR_0603_1K")
      (footprint "eagle-import:0603-RES")
      (fields
        (field (name "MANUFACTURER") "TE Connectivity Passive Product")
        (field (name "MPN") " CPF-A-0603B1K0E")
        (field (name "POWER") "0.0625W")
        (field (name "RESISTANCE") "1k")
      )
      (libsource (lib "eagle-import") (part "RESISTOR_?_06031K"))
    )
    (comp (ref "R34")
      (value "RESISTOR_0603_22")
      (footprint "eagle-import:0603-RES")
      (fields
        (field (name "MANUFACTURER") "Yageo")
        (field (name "MPN") "RC0603FR-0722RL")
        (field (name "POWER") "0.1W")
        (field (name "RESISTANCE") "22")
      )
      (libsource (lib "eagle-import") (part "RESISTOR_?_060322"))
    )
    (comp (ref "R35")
      (value "RESISTOR_0603_1K")
      (footprint "eagle-import:0603-RES")
      (fields
        (field (name "MANUFACTURER") "TE Connectivity Passive Product")
        (field (name "MPN") " CPF-A-0603B1K0E")
        (field (name "POWER") "0.0625W")
        (field (name "RESISTANCE") "1k")
      )
      (libsource (lib "eagle-import") (part "RESISTOR_?_06031K"))
    )
    (comp (ref "R37")
      (value "RESISTOR_0603_22")
      (footprint "eagle-import:0603-RES")
      (fields
        (field (name "MANUFACTURER") "Yageo")
        (field (name "MPN") "RC0603FR-0722RL")
        (field (name "POWER") "0.1W")
        (field (name "RESISTANCE") "22")
      )
      (libsource (lib "eagle-import") (part "RESISTOR_?_060322"))
    )
    (comp (ref "R38")
      (value "RESISTOR_0603_2K")
      (footprint "eagle-import:0603-RES")
      (fields
        (field (name "MANUFACTURER") "Panasonic Electronic Components")
        (field (name "MPN") "ERJ-UP3F2001V")
        (field (name "POWER") "0.25W")
        (field (name "RESISTANCE") "2k")
      )
      (libsource (lib "eagle-import") (part "RESISTOR_?_06032K"))
    )
    (comp (ref "SHDN_B")
      (value "LED_0603_ORANGE")
      (footprint "eagle-import:0603-LED")
      (fields
        (field (name "COLOR") "Orange")
        (field (name "MANUFACTURER") "Kingbright")
        (field (name "MPN") "APT1608SECK")
      )
      (libsource (lib "eagle-import") (part "LED_?_0603ORANGE"))
    )
    (comp (ref "SHDN_BTN")
      (value "CONNECTOR-2_μF_T_V_")
      (footprint "eagle-import:MOLEX_MICROFIT_PTH_VERTICAL_02_DUAL")
      (fields (field (name "MANUFACTURER") "Molex") (field (name "MPN") "436500217"))
      (libsource (lib "eagle-import") (part "CONNECTOR-2_?_μF_T_VBLACK"))
    )
    (comp (ref "SHDN_C")
      (value "LED_0603_ORANGE")
      (footprint "eagle-import:0603-LED")
      (fields
        (field (name "COLOR") "Orange")
        (field (name "MANUFACTURER") "Kingbright")
        (field (name "MPN") "APT1608SECK")
      )
      (libsource (lib "eagle-import") (part "LED_?_0603ORANGE"))
    )
    (comp (ref "SHDN_D")
      (value "LED_0603_ORANGE")
      (footprint "eagle-import:0603-LED")
      (fields
        (field (name "COLOR") "Orange")
        (field (name "MANUFACTURER") "Kingbright")
        (field (name "MPN") "APT1608SECK")
      )
      (libsource (lib "eagle-import") (part "LED_?_0603ORANGE"))
    )
    (comp (ref "SHDN_E")
      (value "LED_0603_ORANGE")
      (footprint "eagle-import:0603-LED")
      (fields
        (field (name "COLOR") "Orange")
        (field (name "MANUFACTURER") "Kingbright")
        (field (name "MPN") "APT1608SECK")
      )
      (libsource (lib "eagle-import") (part "LED_?_0603ORANGE"))
    )
    (comp (ref "SHDN_F")
      (value "LED_0603_ORANGE")
      (footprint "eagle-import:0603-LED")
      (fields
        (field (name "COLOR") "Orange")
        (field (name "MANUFACTURER") "Kingbright")
        (field (name "MPN") "APT1608SECK")
      )
      (libsource (lib "eagle-import") (part "LED_?_0603ORANGE"))
    )
    (comp (ref "STATUS_4.0")
      (value "LED_0603_RED")
      (footprint "eagle-import:0603-LED")
      (fields
        (field (name "COLOR") "Red")
        (field (name "MANUFACTURER") "Kingbright")
        (field (name "MPN") "APT1608SECK/J3-PRV")
      )
      (libsource (lib "eagle-import") (part "LED_?_0603RED"))
    )
    (comp (ref "STATUS_4.1")
      (value "LED_0603_RED")
      (footprint "eagle-import:0603-LED")
      (fields
        (field (name "COLOR") "Red")
        (field (name "MANUFACTURER") "Kingbright")
        (field (name "MPN") "APT1608SECK/J3-PRV")
      )
      (libsource (lib "eagle-import") (part "LED_?_0603RED"))
    )
    (comp (ref "TP1")
      (value "TEST_POINT")
      (footprint "eagle-import:5015")
      (fields (field (name "MPN") "5015") (field (name "MANUFACTURER") "Keystone Electronics"))
      (libsource (lib "eagle-import") (part "TEST_POINT"))
    )
    (comp (ref "TP2")
      (value "TEST_POINT")
      (footprint "eagle-import:5015")
      (fields (field (name "MPN") "5015") (field (name "MANUFACTURER") "Keystone Electronics"))
      (libsource (lib "eagle-import") (part "TEST_POINT"))
    )
    (comp (ref "TP3")
      (value "TEST_POINT")
      (footprint "eagle-import:5015")
      (fields (field (name "MPN") "5015") (field (name "MANUFACTURER") "Keystone Electronics"))
      (libsource (lib "eagle-import") (part "TEST_POINT"))
    )
    (comp (ref "TP4")
      (value "TEST_POINT")
      (footprint "eagle-import:5015")
      (fields (field (name "MPN") "5015") (field (name "MANUFACTURER") "Keystone Electronics"))
      (libsource (lib "eagle-import") (part "TEST_POINT"))
    )
    (comp (ref "TP5")
      (value "TEST_POINT")
      (footprint "eagle-import:5015")
      (fields (field (name "MPN") "5015") (field (name "MANUFACTURER") "Keystone Electronics"))
      (libsource (lib "eagle-import") (part "TEST_POINT"))
    )
    (comp (ref "TP6")
      (value "TEST_POINT")
      (footprint "eagle-import:5015")
      (fields (field (name "MPN") "5015") (field (name "MANUFACTURER") "Keystone Electronics"))
      (libsource (lib "eagle-import") (part "TEST_POINT"))
    )
    (comp (ref "TP7")
      (value "TEST_POINT")
      (footprint "eagle-import:5015")
      (fields (field (name "MPN") "5015") (field (name "MANUFACTURER") "Keystone Electronics"))
      (libsource (lib "eagle-import") (part "TEST_POINT"))
    )
    (comp (ref "TP8")
      (value "TEST_POINT")
      (footprint "eagle-import:5015")
      (fields (field (name "MPN") "5015") (field (name "MANUFACTURER") "Keystone Electronics"))
      (libsource (lib "eagle-import") (part "TEST_POINT"))
    )
    (comp (ref "TP9")
      (value "TEST_POINT")
      (footprint "eagle-import:5015")
      (fields (field (name "MPN") "5015") (field (name "MANUFACTURER") "Keystone Electronics"))
      (libsource (lib "eagle-import") (part "TEST_POINT"))
    )
    (comp (ref "TP10")
      (value "TEST_POINT")
      (footprint "eagle-import:5015")
      (fields (field (name "MPN") "5015") (field (name "MANUFACTURER") "Keystone Electronics"))
      (libsource (lib "eagle-import") (part "TEST_POINT"))
    )
    (comp (ref "TP11")
      (value "TEST_POINT")
      (footprint "eagle-import:5015")
      (fields (field (name "MPN") "5015") (field (name "MANUFACTURER") "Keystone Electronics"))
      (libsource (lib "eagle-import") (part "TEST_POINT"))
    )
    (comp (ref "TP12")
      (value "TEST_POINT")
      (footprint "eagle-import:5015")
      (fields (field (name "MPN") "5015") (field (name "MANUFACTURER") "Keystone Electronics"))
      (libsource (lib "eagle-import") (part "TEST_POINT"))
    )
    (comp (ref "TP13")
      (value "TEST_POINT")
      (footprint "eagle-import:5015")
      (fields (field (name "MPN") "5015") (field (name "MANUFACTURER") "Keystone Electronics"))
      (libsource (lib "eagle-import") (part "TEST_POINT"))
    )
    (comp (ref "U$4")
      (value "RELAY_SOLIDSTATE_NO")
      (footprint "eagle-import:DIP-4@1")
      (fields (field (name "MPN") "AQY214EHA") (field (name "MANUFACTURER") "AQY214EHA"))
      (libsource (lib "eagle-import") (part "RELAY_SOLIDSTATE_NO"))
    )
  )
  (nets
    (net (code "1") (name "+5V") (class "Default")
      (node (ref "5V_PWR") (pin "2") (pinfunction "A_2") (pintype "passive"))
      (node (ref "A1") (pin "VIN") (pinfunction "VIN_VIN") (pintype "power_in"))
      (node (ref "A2") (pin "VIN") (pinfunction "VIN_VIN") (pintype "power_in"))
      (node (ref "C101") (pin "2") (pinfunction "2_2") (pintype "passive"))
      (node (ref "C103") (pin "2") (pinfunction "2_2") (pintype "passive"))
      (node (ref "C4") (pin "2") (pinfunction "2_2") (pintype "passive"))
      (node (ref "C5") (pin "1") (pinfunction "1_1") (pintype "passive"))
      (node (ref "C6") (pin "1") (pinfunction "1_1") (pintype "passive"))
      (node (ref "LATCH") (pin "2") (pinfunction "A_2") (pintype "passive"))
      (node (ref "TP12") (pin "1") (pinfunction "1_1") (pintype "passive"))
      (node (ref "U3") (pin "3") (pinfunction "OUT_3") (pintype "power_in"))
      (node (ref "U4") (pin "3") (pinfunction "VDD_3") (pintype "power_in"))
      (node (ref "U5") (pin "3") (pinfunction "VDD_3") (pintype "power_in"))
    )
    (net (code "2") (name "+24V") (class "Default")
      (node (ref "C7") (pin "1") (pinfunction "1_1") (pintype "passive"))
      (node (ref "J1") (pin "1") (pinfunction "1_1") (pintype "passive"))
      (node (ref "MAIN_CONNECTOR") (pin "4") (pinfunction "4_4") (pintype "passive"))
      (node (ref "R17") (pin "1") (pinfunction "1_1") (pintype "passive"))
      (node (ref "TP13") (pin "1") (pinfunction "1_1") (pintype "passive"))
      (node (ref "U$4") (pin "4") (pinfunction "CONTACT2_4") (pintype "bidirectional"))
      (node (ref "U3") (pin "1") (pinfunction "IN_1") (pintype "power_in"))
      (node (ref "XF1") (pin "3") (pinfunction "2_3") (pintype "passive"))
      (node (ref "XF1") (pin "4") (pinfunction "2_4") (pintype "passive"))
    )
    (net (code "3") (name "4.0_CRX") (class "Default")
      (node (ref "A2") (pin "D0") (pinfunction "(CRX1)D0_D0") (pintype "bidirectional"))
      (node (ref "A2") (pin "D4") (pinfunction "D4_D4") (pintype "bidirectional"))
      (node (ref "U4") (pin "4") (pinfunction "RXD_4") (pintype "output"))
    )
    (net (code "4") (name "4.0_CTX") (class "Default")
      (node (ref "A2") (pin "D1") (pinfunction "(CTX1)D1_D1") (pintype "bidirectional"))
      (node (ref "A2") (pin "D3") (pinfunction "D3_D3") (pintype "bidirectional"))
      (node (ref "U4") (pin "1") (pinfunction "TXD_1") (pintype "input"))
    )
    (net (code "5") (name "4.1_CRX") (class "Default")
      (node (ref "A1") (pin "D0") (pinfunction "(CRX1)D0_D0") (pintype "bidirectional"))
      (node (ref "A1") (pin "D4") (pinfunction "D4_D4") (pintype "bidirectional"))
      (node (ref "U5") (pin "4") (pinfunction "RXD_4") (pintype "output"))
    )
    (net (code "6") (name "4.1_CTX") (class "Default")
      (node (ref "A1") (pin "D1") (pinfunction "(CTX1)D1_D1") (pintype "bidirectional"))
      (node (ref "A1") (pin "D3") (pinfunction "D3_D3") (pintype "bidirectional"))
      (node (ref "U5") (pin "1") (pinfunction "TXD_1") (pintype "input"))
    )
    (net (code "7") (name "24V_READ") (class "Default")
      (node (ref "A1") (pin "D20") (pinfunction "A6_D20") (pintype "bidirectional"))
      (node (ref "A2") (pin "D20") (pinfunction "A6_D20") (pintype "bidirectional"))
      (node (ref "R10") (pin "1") (pinfunction "1_1") (pintype "passive"))
      (node (ref "R17") (pin "2") (pinfunction "2_2") (pintype "passive"))
    )
    (net (code "8") (name "BMS_OK") (class "Default")
      (node (ref "BMS_OK") (pin "2") (pinfunction "A_2") (pintype "passive"))
      (node (ref "D101") (pin "2") (pinfunction "C_2") (pintype "passive"))
      (node (ref "MAIN_CONNECTOR") (pin "6") (pinfunction "6_6") (pintype "passive"))
      (node (ref "R34") (pin "2") (pinfunction "2_2") (pintype "passive"))
      (node (ref "TP7") (pin "1") (pinfunction "1_1") (pintype "passive"))
    )
    (net (code "9") (name "CANH") (class "Default")
      (node (ref "CAN_TERM") (pin "2") (pinfunction "2_2") (pintype "passive"))
      (node (ref "CHG_CAN") (pin "4") (pinfunction "4_4") (pintype "passive"))
      (node (ref "D100") (pin "1") (pinfunction "C1_1") (pintype "passive"))
      (node (ref "J1") (pin "2") (pinfunction "2_2") (pintype "passive"))
      (node (ref "MAIN_CONNECTOR") (pin "1") (pinfunction "1_1") (pintype "passive"))
      (node (ref "U4") (pin "7") (pinfunction "CANH_7") (pintype "output"))
      (node (ref "U5") (pin "7") (pinfunction "CANH_7") (pintype "output"))
    )
    (net (code "10") (name "CANL") (class "Default")
      (node (ref "CHG_CAN") (pin "5") (pinfunction "5_5") (pintype "passive"))
      (node (ref "D100") (pin "2") (pinfunction "C2_2") (pintype "passive"))
      (node (ref "J1") (pin "3") (pinfunction "3_3") (pintype "passive"))
      (node (ref "MAIN_CONNECTOR") (pin "2") (pinfunction "2_2") (pintype "passive"))
      (node (ref "R40") (pin "1") (pinfunction "1_1") (pintype "passive"))
      (node (ref "U4") (pin "6") (pinfunction "CANL_6") (pintype "bidirectional"))
      (node (ref "U5") (pin "6") (pinfunction "CANL_6") (pintype "bidirectional"))
    )
    (net (code "11") (name "CCU_OK") (class "Default")
      (node (ref "CCU_OK") (pin "2") (pinfunction "A_2") (pintype "passive"))
      (node (ref "R30") (pin "2") (pinfunction "2_2") (pintype "passive"))
      (node (ref "R31") (pin "2") (pinfunction "2_2") (pintype "passive"))
      (node (ref "TP9") (pin "1") (pinfunction "1_1") (pintype "passive"))
      (node (ref "U1") (pin "4") (pinfunction "OUT_4") (pintype "output"))
    )
    (net (code "12") (name "GND") (class "Default")
      (node (ref "A1") (pin "AGND/GND") (pinfunction "GND_AGND/GND") (pintype "bidirectional"))
      (node (ref "A1") (pin "GND") (pinfunction "GND_GND") (pintype "bidirectional"))
      (node (ref "A1") (pin "GND@2") (pinfunction "GND_GND@2") (pintype "bidirectional"))
      (node (ref "A2") (pin "AGND/GND") (pinfunction "GND_AGND/GND") (pintype "power_in"))
      (node (ref "A2") (pin "GND") (pinfunction "GND_GND") (pintype "power_in"))
      (node (ref "C1") (pin "1") (pinfunction "1_1") (pintype "passive"))
      (node (ref "C100") (pin "1") (pinfunction "1_1") (pintype "passive"))
      (node (ref "C101") (pin "1") (pinfunction "1_1") (pintype "passive"))
      (node (ref "C102") (pin "1") (pinfunction "1_1") (pintype "passive"))
      (node (ref "C103") (pin "1") (pinfunction "1_1") (pintype "passive"))
      (node (ref "C2") (pin "1") (pinfunction "1_1") (pintype "passive"))
      (node (ref "C3") (pin "1") (pinfunction "1_1") (pintype "passive"))
      (node (ref "C4") (pin "1") (pinfunction "1_1") (pintype "passive"))
      (node (ref "C5") (pin "2") (pinfunction "2_2") (pintype "passive"))
      (node (ref "C6") (pin "2") (pinfunction "2_2") (pintype "passive"))
      (node (ref "C7") (pin "2") (pinfunction "2_2") (pintype "passive"))
      (node (ref "C8") (pin "2") (pinfunction "2_2") (pintype "passive"))
      (node (ref "CHG_CAN") (pin "6") (pinfunction "6_6") (pintype "passive"))
      (node (ref "D100") (pin "3") (pinfunction "A_3") (pintype "passive"))
      (node (ref "D101") (pin "1") (pinfunction "A_1") (pintype "passive"))
      (node (ref "D102") (pin "1") (pinfunction "A_1") (pintype "passive"))
      (node (ref "D3") (pin "1") (pinfunction "C_1") (pintype "passive"))
      (node (ref "D5") (pin "1") (pinfunction "A_1") (pintype "passive"))
      (node (ref "J1") (pin "4") (pinfunction "4_4") (pintype "passive"))
      (node (ref "K1") (pin "14") (pinfunction "4_14") (pintype "bidirectional"))
      (node (ref "K2") (pin "14") (pinfunction "4_14") (pintype "bidirectional"))
      (node (ref "K3") (pin "14") (pinfunction "4_14") (pintype "bidirectional"))
      (node (ref "LATCH_BUTTON") (pin "3") (pinfunction "S_3") (pintype "passive"))
      (node (ref "LATCH_BUTTON") (pin "4") (pinfunction "S_4") (pintype "passive"))
      (node (ref "MAIN_CONNECTOR") (pin "3") (pinfunction "3_3") (pintype "passive"))
      (node (ref "POWER") (pin "2") (pinfunction "2_2") (pintype "passive"))
      (node (ref "R1") (pin "2") (pinfunction "2_2") (pintype "passive"))
      (node (ref "R10") (pin "2") (pinfunction "2_2") (pintype "passive"))
      (node (ref "R11") (pin "2") (pinfunction "2_2") (pintype "passive"))
      (node (ref "R12") (pin "2") (pinfunction "2_2") (pintype "passive"))
      (node (ref "R13") (pin "2") (pinfunction "2_2") (pintype "passive"))
      (node (ref "R14") (pin "2") (pinfunction "2_2") (pintype "passive"))
      (node (ref "R15") (pin "2") (pinfunction "2_2") (pintype "passive"))
      (node (ref "R16") (pin "2") (pinfunction "2_2") (pintype "passive"))
      (node (ref "R2") (pin "2") (pinfunction "2_2") (pintype "passive"))
      (node (ref "R26") (pin "2") (pinfunction "2_2") (pintype "passive"))
      (node (ref "R27") (pin "2") (pinfunction "2_2") (pintype "passive"))
      (node (ref "R28") (pin "2") (pinfunction "2_2") (pintype "passive"))
      (node (ref "R29") (pin "1") (pinfunction "1_1") (pintype "passive"))
      (node (ref "R30") (pin "1") (pinfunction "1_1") (pintype "passive"))
      (node (ref "R32") (pin "2") (pinfunction "2_2") (pintype "passive"))
      (node (ref "R7") (pin "2") (pinfunction "2_2") (pintype "passive"))
      (node (ref "R8") (pin "2") (pinfunction "2_2") (pintype "passive"))
      (node (ref "R9") (pin "2") (pinfunction "2_2") (pintype "passive"))
      (node (ref "SHDN_B") (pin "1") (pinfunction "C_1") (pintype "passive"))
      (node (ref "SHDN_C") (pin "1") (pinfunction "C_1") (pintype "passive"))
      (node (ref "SHDN_D") (pin "1") (pinfunction "C_1") (pintype "passive"))
      (node (ref "SHDN_E") (pin "1") (pinfunction "C_1") (pintype "passive"))
      (node (ref "TP1") (pin "1") (pinfunction "1_1") (pintype "passive"))
      (node (ref "U$100") (pin "2") (pinfunction "CONTROL-_2") (pintype "passive"))
      (node (ref "U$100") (pin "3") (pinfunction "CONTACT1_3") (pintype "bidirectional"))
      (node (ref "U$4") (pin "2") (pinfunction "CONTROL-_2") (pintype "passive"))
      (node (ref "U1") (pin "3") (pinfunction "GND_3") (pintype "power_in"))
      (node (ref "U2") (pin "2") (pinfunction "GND_2") (pintype "power_in"))
      (node (ref "U3") (pin "2") (pinfunction "GND_2") (pintype "power_in"))
      (node (ref "U4") (pin "2") (pinfunction "GND_2") (pintype "power_in"))
      (node (ref "U4") (pin "8") (pinfunction "S_8") (pintype "input"))
      (node (ref "U5") (pin "2") (pinfunction "GND_2") (pintype "power_in"))
      (node (ref "U5") (pin "8") (pinfunction "S_8") (pintype "input"))
      (node (ref "XB1") (pin "2") (pinfunction "MINUS_2") (pintype "power_in"))
    )
    (net (code "13") (name "IMD_OK") (class "Default")
      (node (ref "D102") (pin "2") (pinfunction "C_2") (pintype "passive"))
      (node (ref "MAIN_CONNECTOR") (pin "5") (pinfunction "5_5") (pintype "passive"))
      (node (ref "OKHS") (pin "2") (pinfunction "A_2") (pintype "passive"))
      (node (ref "R25") (pin "2") (pinfunction "2_2") (pintype "passive"))
      (node (ref "TP8") (pin "1") (pinfunction "1_1") (pintype "passive"))
    )
    (net (code "14") (name "LATCH_BUTTON") (class "Default")
      (node (ref "D1") (pin "C") (pinfunction "C_C") (pintype "passive"))
      (node (ref "D2") (pin "C") (pinfunction "C_C") (pintype "passive"))
      (node (ref "D4") (pin "C") (pinfunction "C_C") (pintype "passive"))
      (node (ref "LATCH_BUTTON") (pin "1") (pinfunction "P_1") (pintype "passive"))
      (node (ref "LATCH_BUTTON") (pin "2") (pinfunction "P_2") (pintype "passive"))
      (node (ref "R35") (pin "2") (pinfunction "2_2") (pintype "passive"))
    )
    (net (code "15") (name "Net-(4.1_ONLY-Pad1)") (class "Default")
      (node (ref "4.1_ONLY") (pin "1") (pinfunction "1_1") (pintype "passive"))
      (node (ref "A1") (pin "3V3") (pinfunction "3.3V_3V3") (pintype "power_in"))
      (node (ref "A1") (pin "3V3@2") (pinfunction "3.3V_3V3@2") (pintype "power_in"))
      (node (ref "A1") (pin "3V3@3") (pinfunction "3.3V_3V3@3") (pintype "power_in"))
    )
    (net (code "16") (name "Net-(5V_PWR-C)") (class "Default")
      (node (ref "5V_PWR") (pin "1") (pinfunction "C_1") (pintype "passive"))
      (node (ref "R32") (pin "1") (pinfunction "1_1") (pintype "passive"))
    )
    (net (code "17") (name "Net-(BMS_OK-C)") (class "Default")
      (node (ref "BMS_OK") (pin "1") (pinfunction "C_1") (pintype "passive"))
      (node (ref "R2") (pin "1") (pinfunction "1_1") (pintype "passive"))
    )
    (net (code "18") (name "Net-(C8-Pad1)") (class "Default")
      (node (ref "C8") (pin "1") (pinfunction "1_1") (pintype "passive"))
      (node (ref "R39") (pin "1") (pinfunction "1_1") (pintype "passive"))
      (node (ref "R40") (pin "2") (pinfunction "2_2") (pintype "passive"))
    )
    (net (code "19") (name "Net-(CAN_TERM-Pad1)") (class "Default")
      (node (ref "CAN_TERM") (pin "1") (pinfunction "1_1") (pintype "passive"))
      (node (ref "R39") (pin "2") (pinfunction "2_2") (pintype "passive"))
    )
    (net (code "20") (name "Net-(CCU_OK-C)") (class "Default")
      (node (ref "CCU_OK") (pin "1") (pinfunction "C_1") (pintype "passive"))
      (node (ref "R9") (pin "1") (pinfunction "1_1") (pintype "passive"))
    )
    (net (code "21") (name "Net-(D3-A)") (class "Default")
      (node (ref "D3") (pin "2") (pinfunction "A_2") (pintype "passive"))
      (node (ref "R38") (pin "2") (pinfunction "2_2") (pintype "passive"))
    )
    (net (code "22") (name "Net-(D5-C)") (class "Default")
      (node (ref "D5") (pin "2") (pinfunction "C_2") (pintype "passive"))
      (node (ref "POWER") (pin "1") (pinfunction "1_1") (pintype "passive"))
      (node (ref "XF1") (pin "1") (pinfunction "1_1") (pintype "passive"))
      (node (ref "XF1") (pin "2") (pinfunction "1_2") (pintype "passive"))
      (node (ref "XF2") (pin "1") (pinfunction "1_1") (pintype "passive"))
      (node (ref "XF2") (pin "2") (pinfunction "1_2") (pintype "passive"))
    )
    (net (code "23") (name "Net-(E_SELECT-Pad2)") (class "Default")
      (node (ref "E_SELECT") (pin "2") (pinfunction "2_2") (pintype "passive"))
      (node (ref "F_SELECT") (pin "2") (pinfunction "2_2") (pintype "passive"))
      (node (ref "R100") (pin "1") (pinfunction "1_1") (pintype "passive"))
    )
    (net (code "24") (name "Net-(K1-3)") (class "Default")
      (node (ref "D1") (pin "A") (pinfunction "A_A") (pintype "passive"))
      (node (ref "D105") (pin "A") (pinfunction "A_A") (pintype "passive"))
      (node (ref "K1") (pin "11") (pinfunction "3_11") (pintype "bidirectional"))
      (node (ref "K1") (pin "A2") (pinfunction "COIL-_A2") (pintype "bidirectional"))
    )
    (net (code "25") (name "Net-(K1-COIL+)") (class "Default")
      (node (ref "D105") (pin "C") (pinfunction "C_C") (pintype "passive"))
      (node (ref "K1") (pin "A1") (pinfunction "COIL+_A1") (pintype "bidirectional"))
      (node (ref "R25") (pin "1") (pinfunction "1_1") (pintype "passive"))
    )
    (net (code "26") (name "Net-(K2-3)") (class "Default")
      (node (ref "D104") (pin "A") (pinfunction "A_A") (pintype "passive"))
      (node (ref "D2") (pin "A") (pinfunction "A_A") (pintype "passive"))
      (node (ref "K2") (pin "11") (pinfunction "3_11") (pintype "bidirectional"))
      (node (ref "K2") (pin "A2") (pinfunction "COIL-_A2") (pintype "bidirectional"))
    )
    (net (code "27") (name "Net-(K2-COIL+)") (class "Default")
      (node (ref "D104") (pin "C") (pinfunction "C_C") (pintype "passive"))
      (node (ref "K2") (pin "A1") (pinfunction "COIL+_A1") (pintype "bidirectional"))
      (node (ref "R34") (pin "1") (pinfunction "1_1") (pintype "passive"))
    )
    (net (code "28") (name "Net-(K3-3)") (class "Default")
      (node (ref "D103") (pin "A") (pinfunction "A_A") (pintype "passive"))
      (node (ref "D4") (pin "A") (pinfunction "A_A") (pintype "passive"))
      (node (ref "K3") (pin "11") (pinfunction "3_11") (pintype "bidirectional"))
      (node (ref "K3") (pin "A2") (pinfunction "COIL-_A2") (pintype "bidirectional"))
    )
    (net (code "29") (name "Net-(K3-COIL+)") (class "Default")
      (node (ref "D103") (pin "C") (pinfunction "C_C") (pintype "passive"))
      (node (ref "K3") (pin "A1") (pinfunction "COIL+_A1") (pintype "bidirectional"))
      (node (ref "R37") (pin "1") (pinfunction "1_1") (pintype "passive"))
    )
    (net (code "30") (name "Net-(LATCH-C)") (class "Default")
      (node (ref "LATCH") (pin "1") (pinfunction "C_1") (pintype "passive"))
      (node (ref "R35") (pin "1") (pinfunction "1_1") (pintype "passive"))
    )
    (net (code "31") (name "Net-(OKHS-C)") (class "Default")
      (node (ref "OKHS") (pin "1") (pinfunction "C_1") (pintype "passive"))
      (node (ref "R7") (pin "1") (pinfunction "1_1") (pintype "passive"))
    )
    (net (code "32") (name "Net-(SHDN_B-A)") (class "Default")
      (node (ref "R3") (pin "2") (pinfunction "2_2") (pintype "passive"))
      (node (ref "SHDN_B") (pin "2") (pinfunction "A_2") (pintype "passive"))
    )
    (net (code "33") (name "Net-(SHDN_C-A)") (class "Default")
      (node (ref "R4") (pin "2") (pinfunction "2_2") (pintype "passive"))
      (node (ref "SHDN_C") (pin "2") (pinfunction "A_2") (pintype "passive"))
    )
    (net (code "34") (name "Net-(SHDN_D-A)") (class "Default")
      (node (ref "R5") (pin "2") (pinfunction "2_2") (pintype "passive"))
      (node (ref "SHDN_D") (pin "2") (pinfunction "A_2") (pintype "passive"))
    )
    (net (code "35") (name "Net-(SHDN_E-A)") (class "Default")
      (node (ref "R6") (pin "2") (pinfunction "2_2") (pintype "passive"))
      (node (ref "SHDN_E") (pin "2") (pinfunction "A_2") (pintype "passive"))
    )
    (net (code "36") (name "Net-(SHDN_F-C)") (class "Default")
      (node (ref "R8") (pin "1") (pinfunction "1_1") (pintype "passive"))
      (node (ref "SHDN_F") (pin "1") (pinfunction "C_1") (pintype "passive"))
    )
    (net (code "37") (name "Net-(STATUS_4.0-C)") (class "Default")
      (node (ref "R26") (pin "1") (pinfunction "1_1") (pintype "passive"))
      (node (ref "STATUS_4.0") (pin "1") (pinfunction "C_1") (pintype "passive"))
    )
    (net (code "38") (name "Net-(STATUS_4.1-C)") (class "Default")
      (node (ref "R1") (pin "1") (pinfunction "1_1") (pintype "passive"))
      (node (ref "STATUS_4.1") (pin "1") (pinfunction "C_1") (pintype "passive"))
    )
    (net (code "39") (name "Net-(U$4-CONTACT1)") (class "Default")
      (node (ref "R37") (pin "2") (pinfunction "2_2") (pintype "passive"))
      (node (ref "R38") (pin "1") (pinfunction "1_1") (pintype "passive"))
      (node (ref "U$4") (pin "3") (pinfunction "CONTACT1_3") (pintype "bidirectional"))
    )
    (net (code "40") (name "Net-(U$4-CONTROL+)") (class "Default")
      (node (ref "R31") (pin "1") (pinfunction "1_1") (pintype "passive"))
      (node (ref "U$4") (pin "1") (pinfunction "CONTROL+_1") (pintype "passive"))
    )
    (net (code "41") (name "Net-(U$100-CONTROL+)") (class "Default")
      (node (ref "R100") (pin "2") (pinfunction "2_2") (pintype "passive"))
      (node (ref "U$100") (pin "1") (pinfunction "CONTROL+_1") (pintype "passive"))
    )
    (net (code "42") (name "Net-(U1A-IN)") (class "Default")
      (node (ref "R27") (pin "1") (pinfunction "1_1") (pintype "passive"))
      (node (ref "U1") (pin "2") (pinfunction "IN_2") (pintype "input"))
      (node (ref "U2") (pin "1") (pinfunction "~{RESET}_1") (pintype "output"))
    )
    (net (code "43") (name "Net-(XB1-PLUS)") (class "Default")
      (node (ref "A1") (pin "VBAT") (pinfunction "VBAT_VBAT") (pintype "power_in"))
      (node (ref "XB1") (pin "1") (pinfunction "PLUS_1") (pintype "power_in"))
    )
    (net (code "44") (name "RPC_SWITCH") (class "Default")
      (node (ref "MAIN_CONNECTOR") (pin "8") (pinfunction "8_8") (pintype "passive"))
      (node (ref "U$100") (pin "4") (pinfunction "CONTACT2_4") (pintype "bidirectional"))
    )
    (net (code "45") (name "SHDN_A") (class "Default")
      (node (ref "K1") (pin "21") (pinfunction "6_21") (pintype "bidirectional"))
      (node (ref "R23") (pin "1") (pinfunction "1_1") (pintype "passive"))
      (node (ref "TP10") (pin "1") (pinfunction "1_1") (pintype "passive"))
      (node (ref "XF2") (pin "3") (pinfunction "2_3") (pintype "passive"))
      (node (ref "XF2") (pin "4") (pinfunction "2_4") (pintype "passive"))
    )
    (net (code "46") (name "SHDN_A_READ") (class "Default")
      (node (ref "A1") (pin "D14") (pinfunction "A0_D14") (pintype "bidirectional"))
      (node (ref "A2") (pin "D14") (pinfunction "A0_D14") (pintype "bidirectional"))
      (node (ref "R16") (pin "1") (pinfunction "1_1") (pintype "passive"))
      (node (ref "R23") (pin "2") (pinfunction "2_2") (pintype "passive"))
    )
    (net (code "47") (name "SHDN_B") (class "Default")
      (node (ref "K1") (pin "24") (pinfunction "5_24") (pintype "bidirectional"))
      (node (ref "K2") (pin "21") (pinfunction "6_21") (pintype "bidirectional"))
      (node (ref "R22") (pin "1") (pinfunction "1_1") (pintype "passive"))
      (node (ref "R3") (pin "1") (pinfunction "1_1") (pintype "passive"))
      (node (ref "TP2") (pin "1") (pinfunction "1_1") (pintype "passive"))
    )
    (net (code "48") (name "SHDN_B_READ") (class "Default")
      (node (ref "A1") (pin "D15") (pinfunction "A1_D15") (pintype "bidirectional"))
      (node (ref "A2") (pin "D15") (pinfunction "A1_D15") (pintype "bidirectional"))
      (node (ref "R15") (pin "1") (pinfunction "1_1") (pintype "passive"))
      (node (ref "R22") (pin "2") (pinfunction "2_2") (pintype "passive"))
    )
    (net (code "49") (name "SHDN_C") (class "Default")
      (node (ref "K2") (pin "24") (pinfunction "5_24") (pintype "bidirectional"))
      (node (ref "K3") (pin "21") (pinfunction "6_21") (pintype "bidirectional"))
      (node (ref "R21") (pin "1") (pinfunction "1_1") (pintype "passive"))
      (node (ref "R4") (pin "1") (pinfunction "1_1") (pintype "passive"))
      (node (ref "TP3") (pin "1") (pinfunction "1_1") (pintype "passive"))
    )
    (net (code "50") (name "SHDN_C_READ") (class "Default")
      (node (ref "A1") (pin "D16") (pinfunction "A2_D16") (pintype "bidirectional"))
      (node (ref "A2") (pin "D16") (pinfunction "A2_D16") (pintype "bidirectional"))
      (node (ref "R14") (pin "1") (pinfunction "1_1") (pintype "passive"))
      (node (ref "R21") (pin "2") (pinfunction "2_2") (pintype "passive"))
    )
    (net (code "51") (name "SHDN_D") (class "Default")
      (node (ref "K3") (pin "24") (pinfunction "5_24") (pintype "bidirectional"))
      (node (ref "R20") (pin "1") (pinfunction "1_1") (pintype "passive"))
      (node (ref "R5") (pin "1") (pinfunction "1_1") (pintype "passive"))
      (node (ref "SHDN_BTN") (pin "1") (pinfunction "1_1") (pintype "passive"))
      (node (ref "TP4") (pin "1") (pinfunction "1_1") (pintype "passive"))
    )
    (net (code "52") (name "SHDN_D_READ") (class "Default")
      (node (ref "A1") (pin "D17") (pinfunction "A3_D17") (pintype "bidirectional"))
      (node (ref "A2") (pin "D17") (pinfunction "A3_D17") (pintype "bidirectional"))
      (node (ref "R13") (pin "1") (pinfunction "1_1") (pintype "passive"))
      (node (ref "R20") (pin "2") (pinfunction "2_2") (pintype "passive"))
    )
    (net (code "53") (name "SHDN_E") (class "Default")
      (node (ref "CHG_CAN") (pin "3") (pinfunction "3_3") (pintype "passive"))
      (node (ref "E_SELECT") (pin "1") (pinfunction "1_1") (pintype "passive"))
      (node (ref "R19") (pin "1") (pinfunction "1_1") (pintype "passive"))
      (node (ref "R6") (pin "1") (pinfunction "1_1") (pintype "passive"))
      (node (ref "SHDN_BTN") (pin "2") (pinfunction "2_2") (pintype "passive"))
      (node (ref "TP5") (pin "1") (pinfunction "1_1") (pintype "passive"))
    )
    (net (code "54") (name "SHDN_E_READ") (class "Default")
      (node (ref "A1") (pin "D18") (pinfunction "A4_D18") (pintype "bidirectional"))
      (node (ref "A2") (pin "D18") (pinfunction "A4_D18") (pintype "bidirectional"))
      (node (ref "R12") (pin "1") (pinfunction "1_1") (pintype "passive"))
      (node (ref "R19") (pin "2") (pinfunction "2_2") (pintype "passive"))
    )
    (net (code "55") (name "SHDN_F") (class "Default")
      (node (ref "CHG_CAN") (pin "1") (pinfunction "1_1") (pintype "passive"))
      (node (ref "CHG_CAN") (pin "2") (pinfunction "2_2") (pintype "passive"))
      (node (ref "F_SELECT") (pin "1") (pinfunction "1_1") (pintype "passive"))
      (node (ref "MAIN_CONNECTOR") (pin "7") (pinfunction "7_7") (pintype "passive"))
      (node (ref "R18") (pin "1") (pinfunction "1_1") (pintype "passive"))
      (node (ref "SHDN_F") (pin "2") (pinfunction "A_2") (pintype "passive"))
      (node (ref "TP6") (pin "1") (pinfunction "1_1") (pintype "passive"))
    )
    (net (code "56") (name "SHDN_F_READ") (class "Default")
      (node (ref "A1") (pin "D19") (pinfunction "A5_D19") (pintype "bidirectional"))
      (node (ref "A2") (pin "D19") (pinfunction "A5_D19") (pintype "bidirectional"))
      (node (ref "R11") (pin "1") (pinfunction "1_1") (pintype "passive"))
      (node (ref "R18") (pin "2") (pinfunction "2_2") (pintype "passive"))
    )
    (net (code "57") (name "STATUS_4.0") (class "Default")
      (node (ref "A2") (pin "D5") (pinfunction "D5_D5") (pintype "bidirectional"))
      (node (ref "STATUS_4.0") (pin "2") (pinfunction "A_2") (pintype "passive"))
    )
    (net (code "58") (name "STATUS_4.1") (class "Default")
      (node (ref "A1") (pin "D5") (pinfunction "D5_D5") (pintype "bidirectional"))
      (node (ref "STATUS_4.1") (pin "2") (pinfunction "A_2") (pintype "passive"))
    )
    (net (code "59") (name "SW_SHUTDOWN") (class "Default")
      (node (ref "A1") (pin "D6") (pinfunction "D6_D6") (pintype "bidirectional"))
      (node (ref "A2") (pin "D6") (pinfunction "D6_D6") (pintype "bidirectional"))
      (node (ref "C1") (pin "2") (pinfunction "2_2") (pintype "passive"))
      (node (ref "R29") (pin "2") (pinfunction "2_2") (pintype "passive"))
      (node (ref "U2") (pin "3") (pinfunction "~{MR}_3") (pintype "input"))
    )
    (net (code "60") (name "VDD") (class "Default")
      (node (ref "4.1_ONLY") (pin "2") (pinfunction "2_2") (pintype "passive"))
      (node (ref "A2") (pin "3.3V") (pinfunction "3.3V_3.3V") (pintype "power_in"))
      (node (ref "C100") (pin "2") (pinfunction "2_2") (pintype "passive"))
      (node (ref "C102") (pin "2") (pinfunction "2_2") (pintype "passive"))
      (node (ref "C2") (pin "2") (pinfunction "2_2") (pintype "passive"))
      (node (ref "C3") (pin "2") (pinfunction "2_2") (pintype "passive"))
      (node (ref "TP11") (pin "1") (pinfunction "1_1") (pintype "passive"))
      (node (ref "U1") (pin "5") (pinfunction "VDD_5") (pintype "power_in"))
      (node (ref "U2") (pin "5") (pinfunction "VDD_5") (pintype "power_in"))
      (node (ref "U4") (pin "5") (pinfunction "VIO_5") (pintype "power_in"))
      (node (ref "U5") (pin "5") (pinfunction "VIO_5") (pintype "power_in"))
    )
    (net (code "61") (name "WATCHDOG_IN") (class "Default")
      (node (ref "A1") (pin "D7") (pinfunction "D7_D7") (pintype "bidirectional"))
      (node (ref "A2") (pin "D7") (pinfunction "D7_D7") (pintype "bidirectional"))
      (node (ref "R28") (pin "1") (pinfunction "1_1") (pintype "passive"))
      (node (ref "U2") (pin "4") (pinfunction "WDI_4") (pintype "input"))
    )
    (net (code "62") (name "unconnected-(A1-(CLK)D13-PadD13)") (class "Default")
      (node (ref "A1") (pin "D13") (pinfunction "(CLK)D13_D13") (pintype "bidirectional"))
    )
    (net (code "63") (name "unconnected-(A1-(CS)D10-PadD10)") (class "Default")
      (node (ref "A1") (pin "D10") (pinfunction "(CS)D10_D10") (pintype "bidirectional"))
    )
    (net (code "64") (name "unconnected-(A1-(SDI)D12-PadD12)") (class "Default")
      (node (ref "A1") (pin "D12") (pinfunction "(SDI)D12_D12") (pintype "bidirectional"))
    )
    (net (code "65") (name "unconnected-(A1-(SDO)D11-PadD11)") (class "Default")
      (node (ref "A1") (pin "D11") (pinfunction "(SDO)D11_D11") (pintype "bidirectional"))
    )
    (net (code "66") (name "unconnected-(A1-A7-PadD21)") (class "Default")
      (node (ref "A1") (pin "D21") (pinfunction "A7_D21") (pintype "bidirectional"))
    )
    (net (code "67") (name "unconnected-(A1-A8-PadD22)") (class "Default")
      (node (ref "A1") (pin "D22") (pinfunction "A8_D22") (pintype "bidirectional"))
    )
    (net (code "68") (name "unconnected-(A1-A9-PadD23)") (class "Default")
      (node (ref "A1") (pin "D23") (pinfunction "A9_D23") (pintype "bidirectional"))
    )
    (net (code "69") (name "unconnected-(A1-A10-PadD24)") (class "Default")
      (node (ref "A1") (pin "D24") (pinfunction "A10_D24") (pintype "bidirectional"))
    )
    (net (code "70") (name "unconnected-(A1-A11-PadD25)") (class "Default")
      (node (ref "A1") (pin "D25") (pinfunction "A11_D25") (pintype "bidirectional"))
    )
    (net (code "71") (name "unconnected-(A1-A12-PadD26)") (class "Default")
      (node (ref "A1") (pin "D26") (pinfunction "A12_D26") (pintype "bidirectional"))
    )
    (net (code "72") (name "unconnected-(A1-A13-PadD27)") (class "Default")
      (node (ref "A1") (pin "D27") (pinfunction "A13_D27") (pintype "bidirectional"))
    )
    (net (code "73") (name "unconnected-(A1-A14-PadD38)") (class "Default")
      (node (ref "A1") (pin "D38") (pinfunction "A14_D38") (pintype "bidirectional"))
    )
    (net (code "74") (name "unconnected-(A1-A15-PadD39)") (class "Default")
      (node (ref "A1") (pin "D39") (pinfunction "A15_D39") (pintype "bidirectional"))
    )
    (net (code "75") (name "unconnected-(A1-A16-PadD40)") (class "Default")
      (node (ref "A1") (pin "D40") (pinfunction "A16_D40") (pintype "bidirectional"))
    )
    (net (code "76") (name "unconnected-(A1-A17-PadD41)") (class "Default")
      (node (ref "A1") (pin "D41") (pinfunction "A17_D41") (pintype "bidirectional"))
    )
    (net (code "77") (name "unconnected-(A1-PadD2)") (class "Default")
      (node (ref "A1") (pin "D2") (pinfunction "D2_D2") (pintype "bidirectional"))
    )
    (net (code "78") (name "unconnected-(A1-PadD8)") (class "Default")
      (node (ref "A1") (pin "D8") (pinfunction "D8_D8") (pintype "bidirectional"))
    )
    (net (code "79") (name "unconnected-(A1-PadD9)") (class "Default")
      (node (ref "A1") (pin "D9") (pinfunction "D9_D9") (pintype "bidirectional"))
    )
    (net (code "80") (name "unconnected-(A1-PadD28)") (class "Default")
      (node (ref "A1") (pin "D28") (pinfunction "D28_D28") (pintype "bidirectional"))
    )
    (net (code "81") (name "unconnected-(A1-PadD29)") (class "Default")
      (node (ref "A1") (pin "D29") (pinfunction "D29_D29") (pintype "bidirectional"))
    )
    (net (code "82") (name "unconnected-(A1-PadD30)") (class "Default")
      (node (ref "A1") (pin "D30") (pinfunction "D30_D30") (pintype "bidirectional"))
    )
    (net (code "83") (name "unconnected-(A1-PadD31)") (class "Default")
      (node (ref "A1") (pin "D31") (pinfunction "D31_D31") (pintype "bidirectional"))
    )
    (net (code "84") (name "unconnected-(A1-PadD32)") (class "Default")
      (node (ref "A1") (pin "D32") (pinfunction "D32_D32") (pintype "bidirectional"))
    )
    (net (code "85") (name "unconnected-(A1-PadD33)") (class "Default")
      (node (ref "A1") (pin "D33") (pinfunction "D33_D33") (pintype "bidirectional"))
    )
    (net (code "86") (name "unconnected-(A1-PadD34)") (class "Default")
      (node (ref "A1") (pin "D34") (pinfunction "D34_D34") (pintype "bidirectional"))
    )
    (net (code "87") (name "unconnected-(A1-PadD35)") (class "Default")
      (node (ref "A1") (pin "D35") (pinfunction "D35_D35") (pintype "bidirectional"))
    )
    (net (code "88") (name "unconnected-(A1-PadD36)") (class "Default")
      (node (ref "A1") (pin "D36") (pinfunction "D36_D36") (pintype "bidirectional"))
    )
    (net (code "89") (name "unconnected-(A1-PadD37)") (class "Default")
      (node (ref "A1") (pin "D37") (pinfunction "D37_D37") (pintype "bidirectional"))
    )
    (net (code "90") (name "unconnected-(A2-(CLK)D13-PadD13)") (class "Default")
      (node (ref "A2") (pin "D13") (pinfunction "(CLK)D13_D13") (pintype "bidirectional"))
    )
    (net (code "91") (name "unconnected-(A2-(CS)D10-PadD10)") (class "Default")
      (node (ref "A2") (pin "D10") (pinfunction "(CS)D10_D10") (pintype "bidirectional"))
    )
    (net (code "92") (name "unconnected-(A2-(SDI)D12-PadD12)") (class "Default")
      (node (ref "A2") (pin "D12") (pinfunction "(SDI)D12_D12") (pintype "bidirectional"))
    )
    (net (code "93") (name "unconnected-(A2-(SDO)D11-PadD11)") (class "Default")
      (node (ref "A2") (pin "D11") (pinfunction "(SDO)D11_D11") (pintype "bidirectional"))
    )
    (net (code "94") (name "unconnected-(A2-A7-PadD21)") (class "Default")
      (node (ref "A2") (pin "D21") (pinfunction "A7_D21") (pintype "bidirectional"))
    )
    (net (code "95") (name "unconnected-(A2-A8-PadD22)") (class "Default")
      (node (ref "A2") (pin "D22") (pinfunction "A8_D22") (pintype "bidirectional"))
    )
    (net (code "96") (name "unconnected-(A2-A9-PadD23)") (class "Default")
      (node (ref "A2") (pin "D23") (pinfunction "A9_D23") (pintype "bidirectional"))
    )
    (net (code "97") (name "unconnected-(A2-PadD2)") (class "Default")
      (node (ref "A2") (pin "D2") (pinfunction "D2_D2") (pintype "bidirectional"))
    )
    (net (code "98") (name "unconnected-(A2-PadD8)") (class "Default")
      (node (ref "A2") (pin "D8") (pinfunction "D8_D8") (pintype "bidirectional"))
    )
    (net (code "99") (name "unconnected-(A2-PadD9)") (class "Default")
      (node (ref "A2") (pin "D9") (pinfunction "D9_D9") (pintype "bidirectional"))
    )
    (net (code "100") (name "unconnected-(K1-2-Pad12)") (class "Default")
      (node (ref "K1") (pin "12") (pinfunction "2_12") (pintype "bidirectional"))
    )
    (net (code "101") (name "unconnected-(K1-7-Pad22)") (class "Default")
      (node (ref "K1") (pin "22") (pinfunction "7_22") (pintype "bidirectional"))
    )
    (net (code "102") (name "unconnected-(K2-2-Pad12)") (class "Default")
      (node (ref "K2") (pin "12") (pinfunction "2_12") (pintype "bidirectional"))
    )
    (net (code "103") (name "unconnected-(K2-7-Pad22)") (class "Default")
      (node (ref "K2") (pin "22") (pinfunction "7_22") (pintype "bidirectional"))
    )
    (net (code "104") (name "unconnected-(K3-2-Pad12)") (class "Default")
      (node (ref "K3") (pin "12") (pinfunction "2_12") (pintype "bidirectional"))
    )
    (net (code "105") (name "unconnected-(K3-7-Pad22)") (class "Default")
      (node (ref "K3") (pin "22") (pinfunction "7_22") (pintype "bidirectional"))
    )
  )
)
